# DDR3_LoongSon.net
KiCad netlist of a schematic drawn in Altium Designer
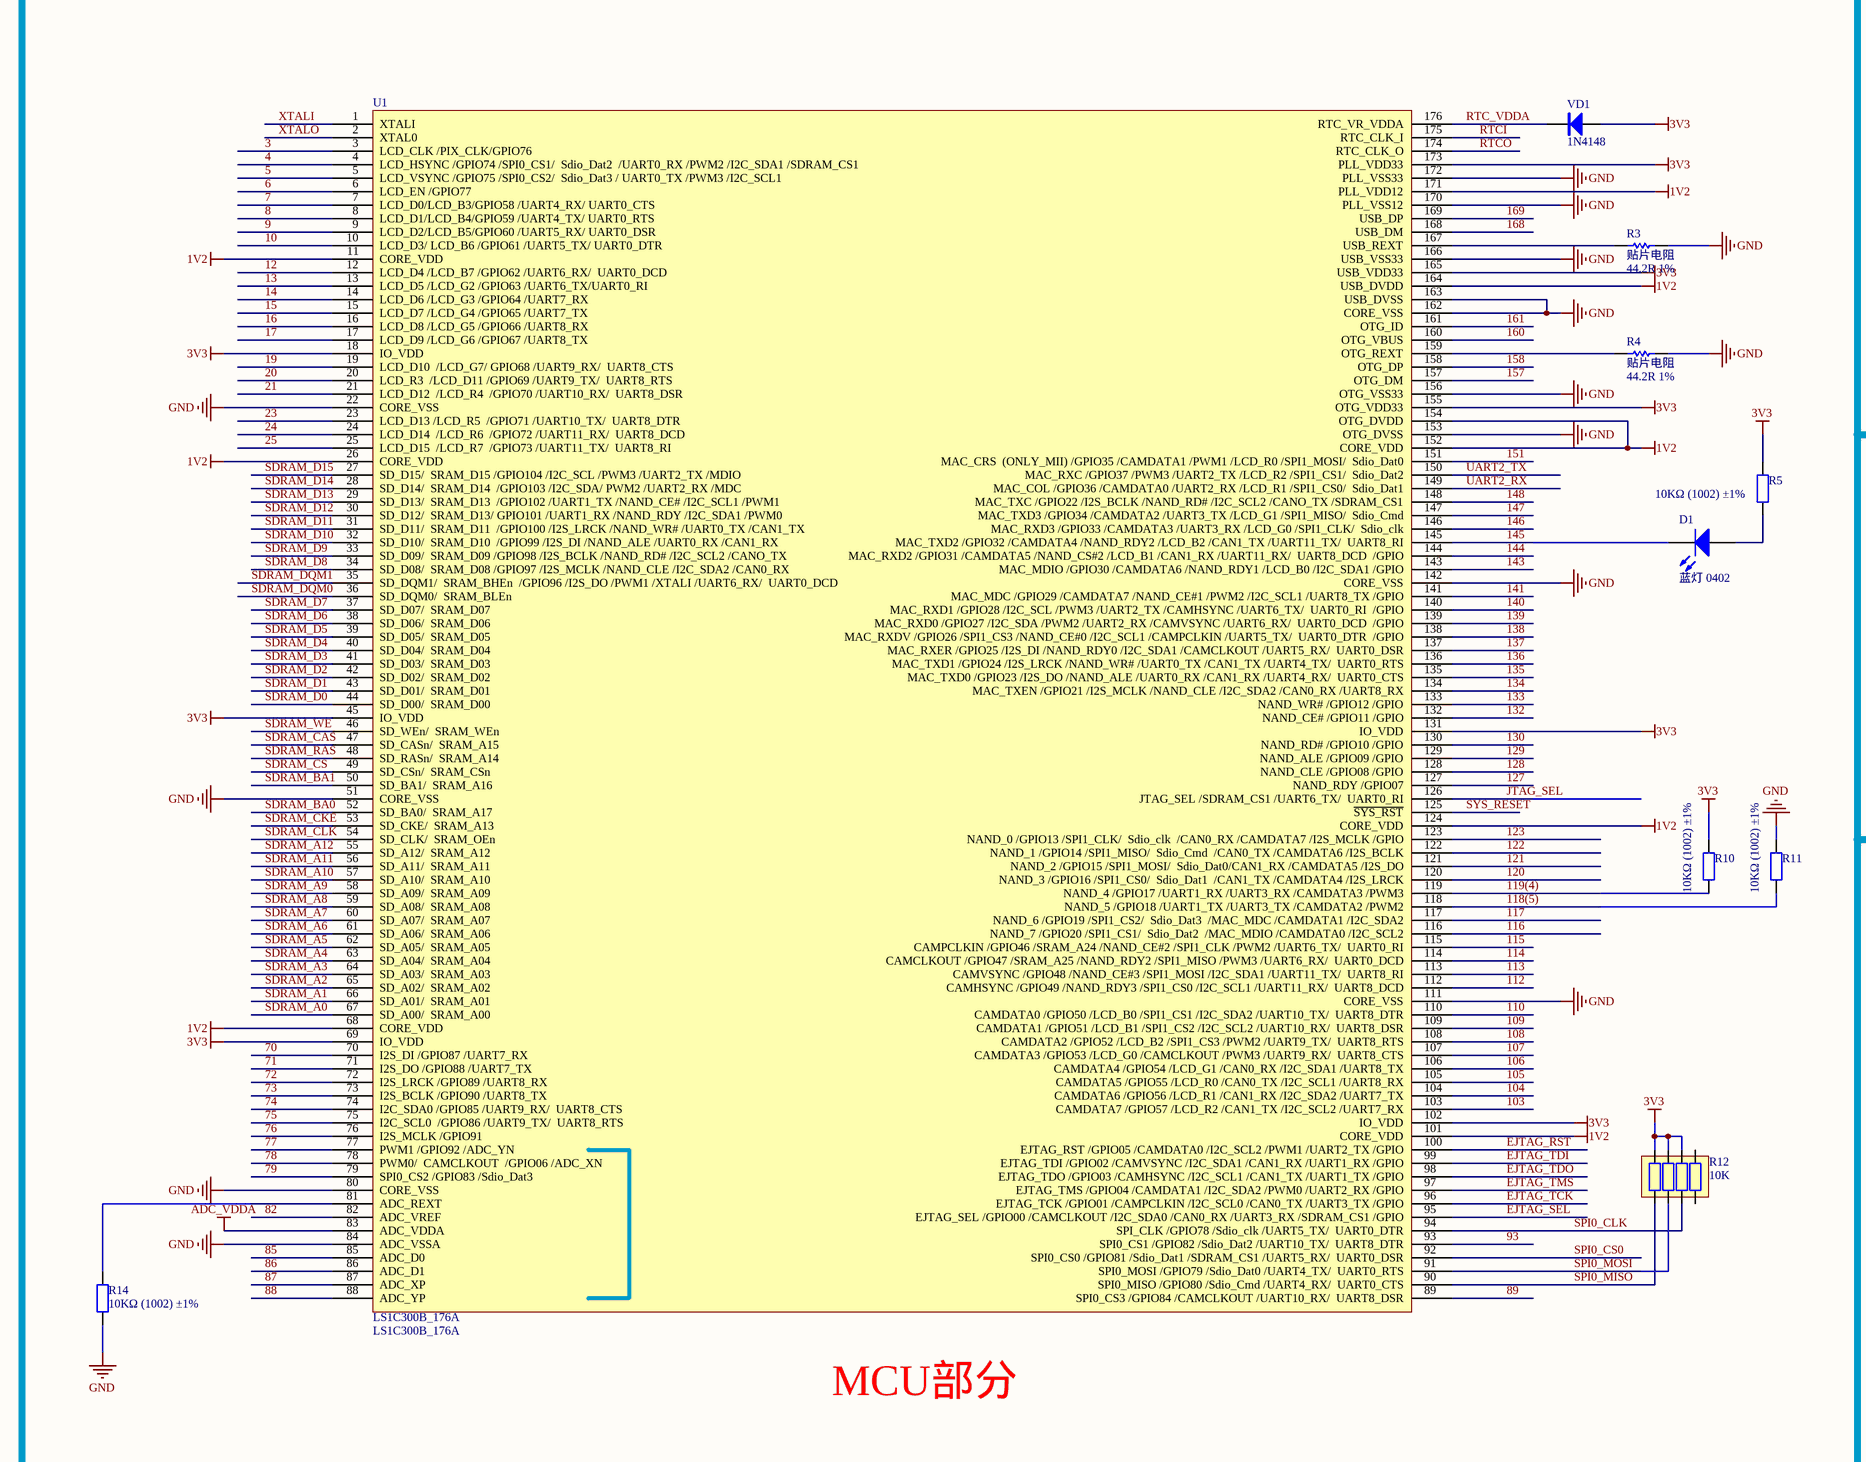
[diagram p0: DDR3_LoongSon.SchDoc, top left]
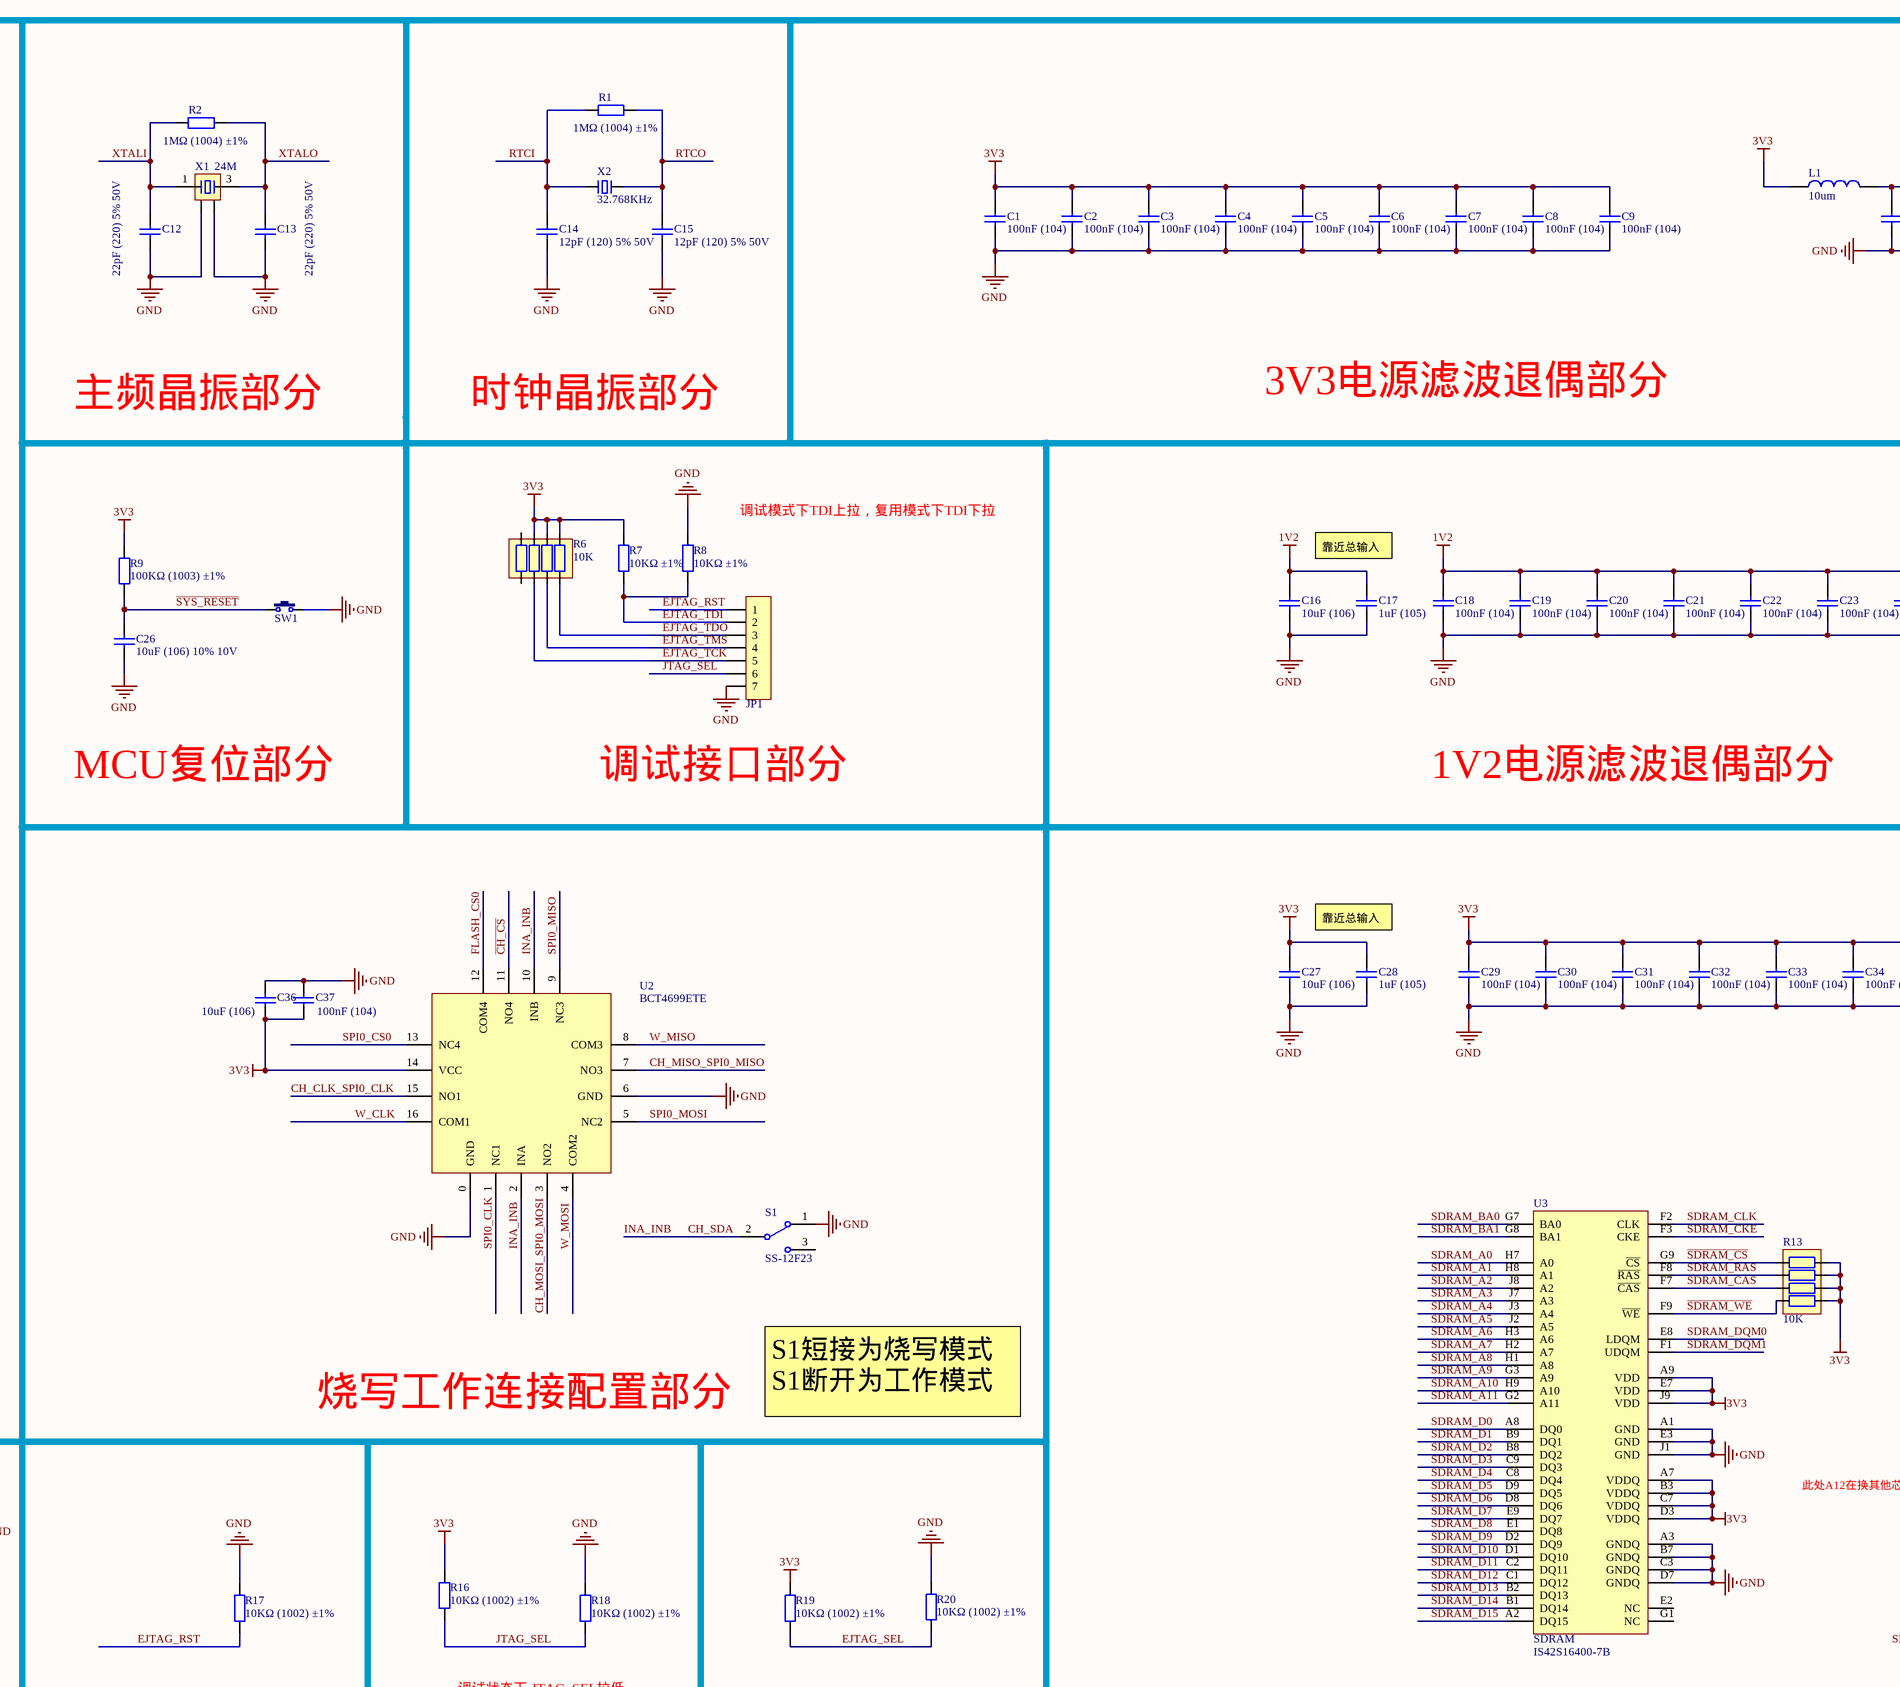
[diagram p1: DDR3_LoongSon.SchDoc, top middle]
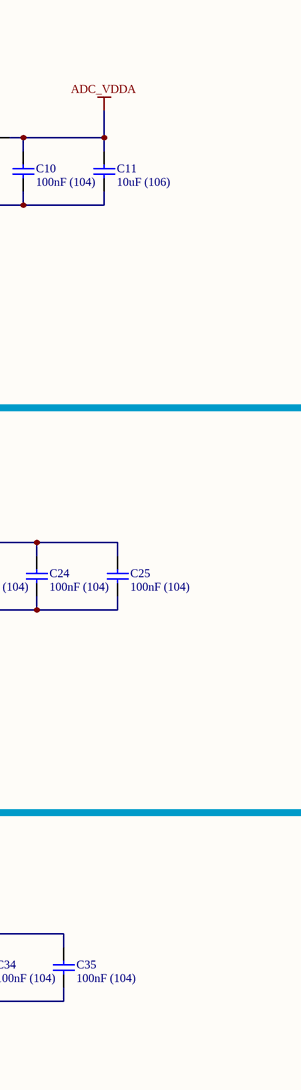
[diagram p2: DDR3_LoongSon.SchDoc, top right]
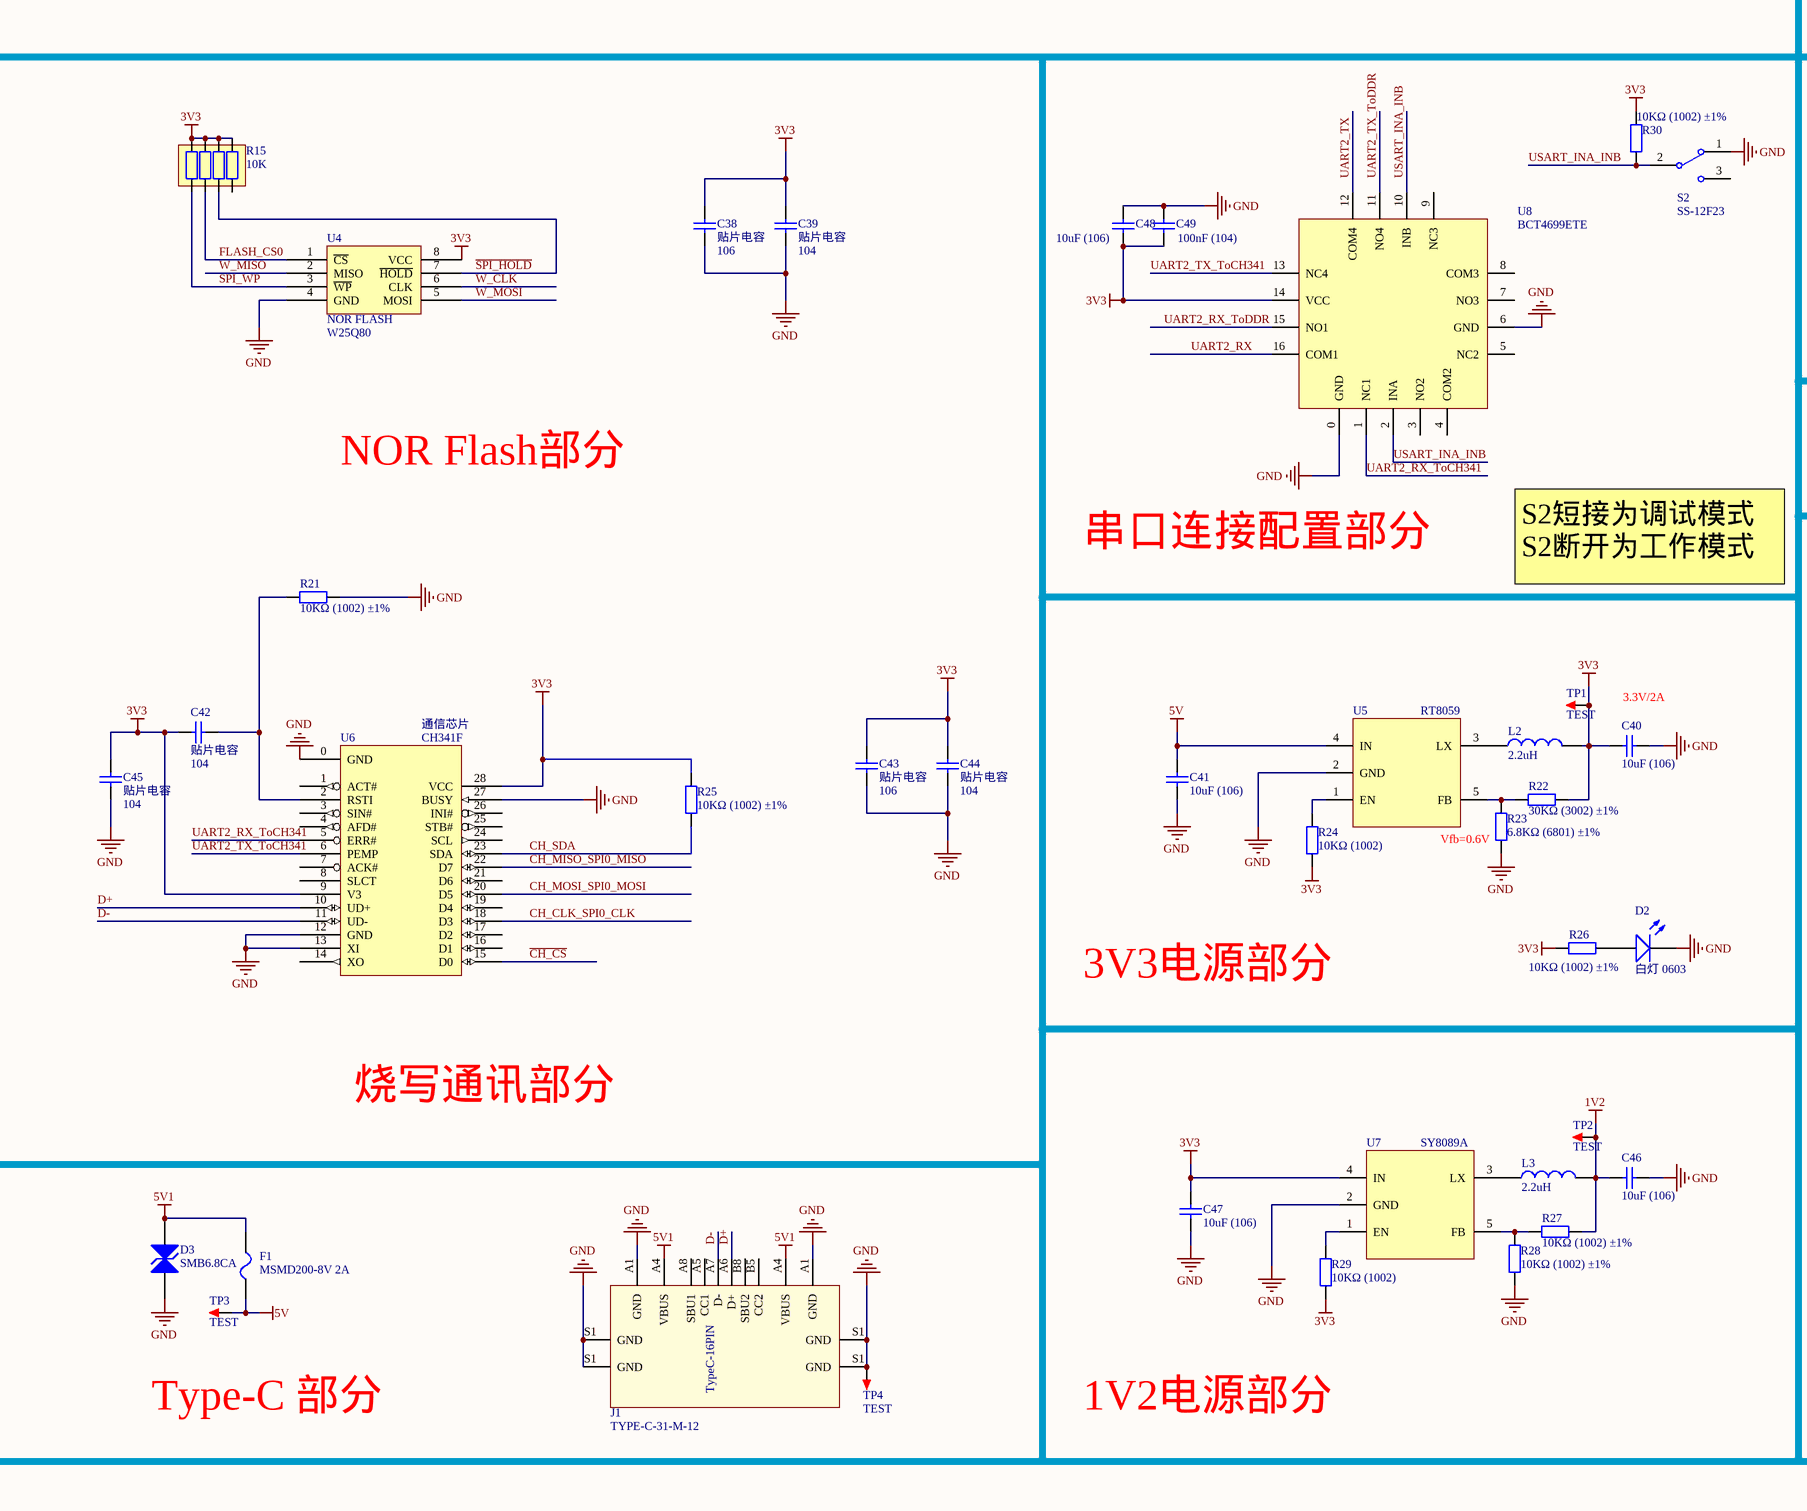
[diagram p3: DDR3_LoongSon.SchDoc, bottom left]
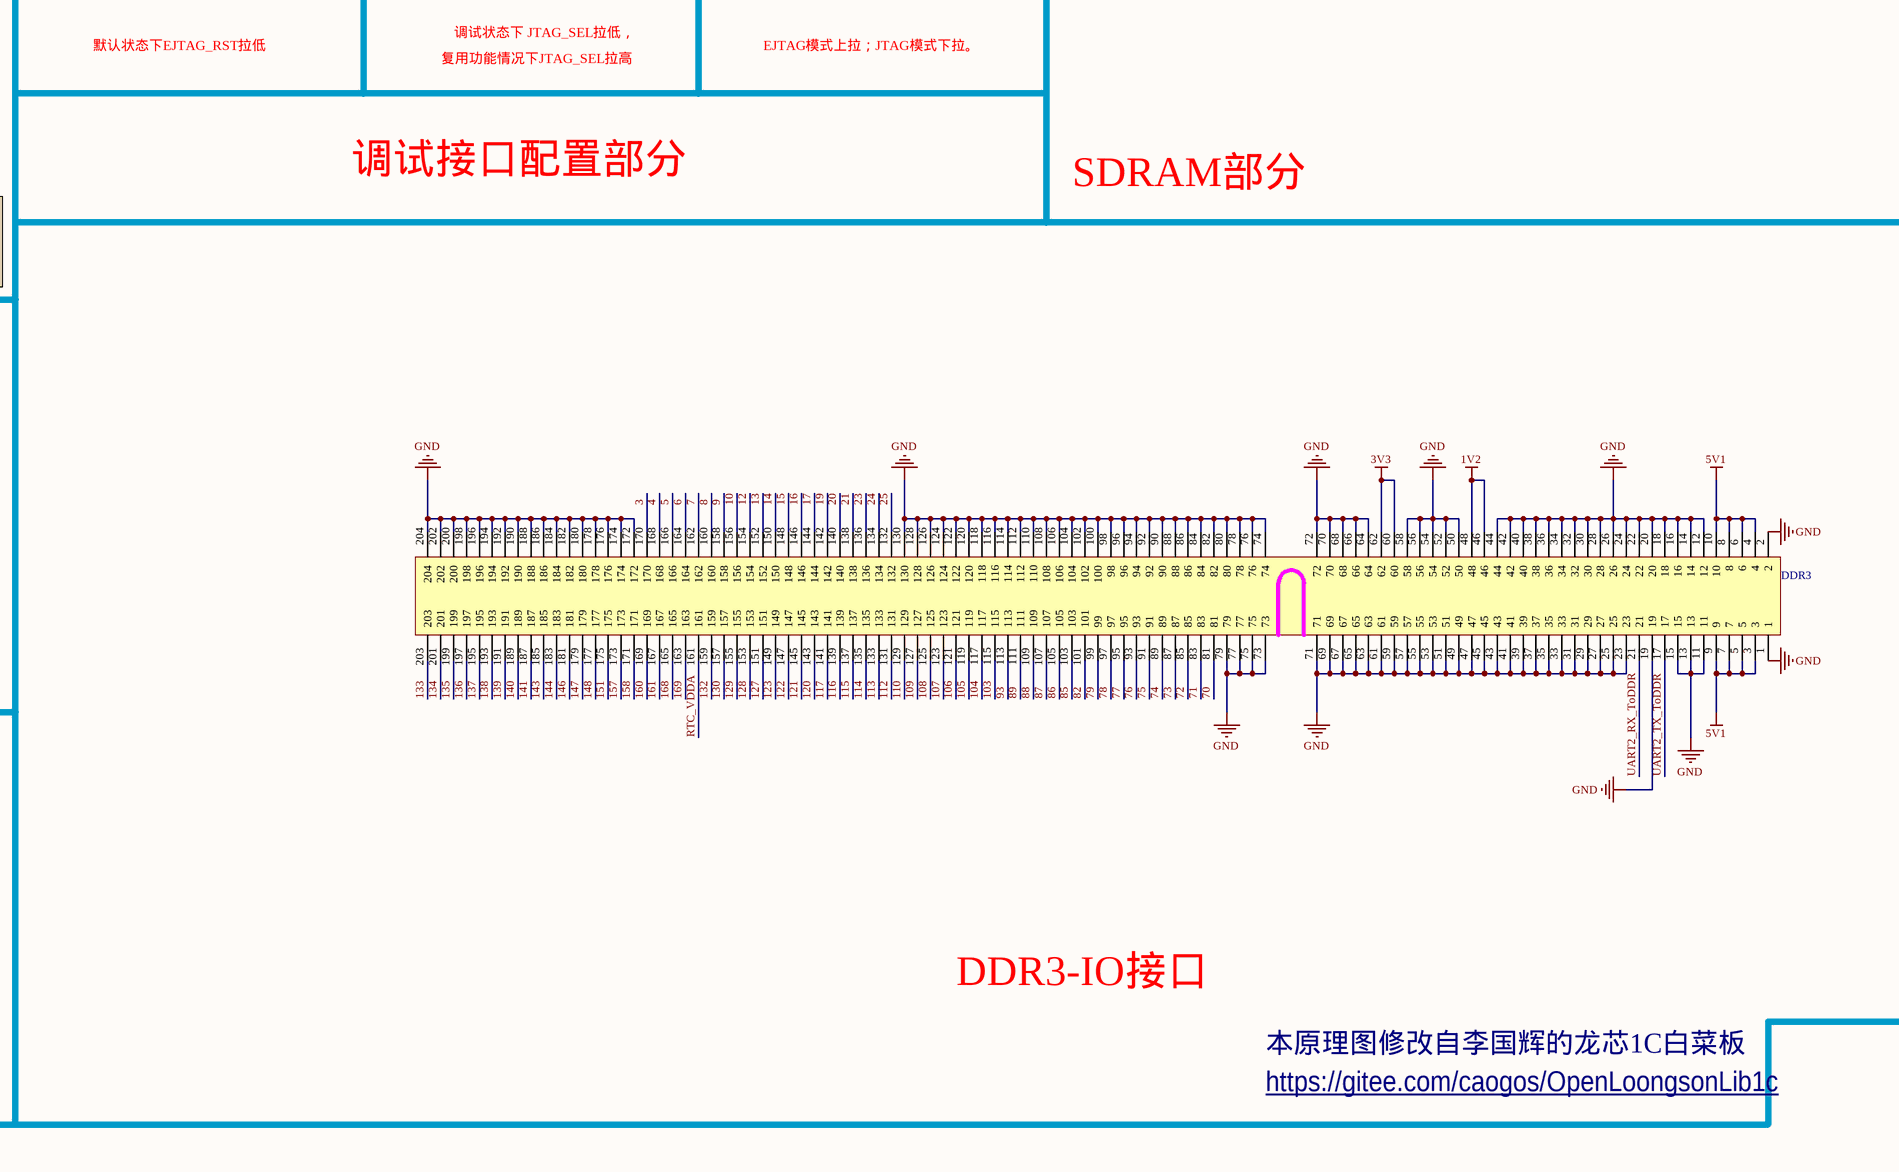
[diagram p4: DDR3_LoongSon.SchDoc, bottom middle]
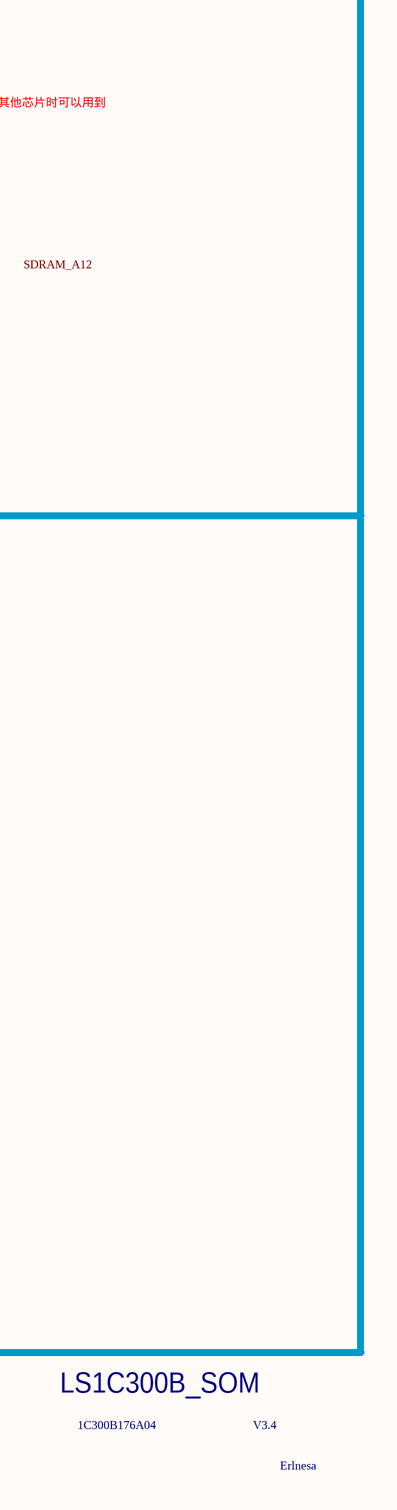
[diagram p5: DDR3_LoongSon.SchDoc, bottom right]

(export (version "E")
  (design (tool "Eeschema 10.0.6"))
  (components
    (comp (ref "C1")
      (value "100nF (104)")
      (footprint "LC-0402_C")
      (description "贴片电容")
      (libsource (lib "Miscellaneous Devices LC") (part "0603 100nF (104) 10% 50V"))
    )
    (comp (ref "C2")
      (value "100nF (104)")
      (footprint "LC-0402_C")
      (description "贴片电容")
      (libsource (lib "Miscellaneous Devices LC") (part "0603 100nF (104) 10% 50V"))
    )
    (comp (ref "C3")
      (value "100nF (104)")
      (footprint "LC-0402_C")
      (description "贴片电容")
      (libsource (lib "Miscellaneous Devices LC") (part "0603 100nF (104) 10% 50V"))
    )
    (comp (ref "C4")
      (value "100nF (104)")
      (footprint "LC-0402_C")
      (description "贴片电容")
      (libsource (lib "Miscellaneous Devices LC") (part "0603 100nF (104) 10% 50V"))
    )
    (comp (ref "C5")
      (value "100nF (104)")
      (footprint "LC-0402_C")
      (description "贴片电容")
      (libsource (lib "Miscellaneous Devices LC") (part "0603 100nF (104) 10% 50V"))
    )
    (comp (ref "C6")
      (value "100nF (104)")
      (footprint "LC-0402_C")
      (description "贴片电容")
      (libsource (lib "Miscellaneous Devices LC") (part "0603 100nF (104) 10% 50V"))
    )
    (comp (ref "C7")
      (value "100nF (104)")
      (footprint "LC-0402_C")
      (description "贴片电容")
      (libsource (lib "Miscellaneous Devices LC") (part "0603 100nF (104) 10% 50V"))
    )
    (comp (ref "C8")
      (value "100nF (104)")
      (footprint "LC-0402_C")
      (description "贴片电容")
      (libsource (lib "Miscellaneous Devices LC") (part "0603 100nF (104) 10% 50V"))
    )
    (comp (ref "C9")
      (value "100nF (104)")
      (footprint "LC-0402_C")
      (description "贴片电容")
      (libsource (lib "Miscellaneous Devices LC") (part "0603 100nF (104) 10% 50V"))
    )
    (comp (ref "C10")
      (value "100nF (104)")
      (footprint "LC-0402_C")
      (description "贴片电容")
      (libsource (lib "Miscellaneous Devices LC") (part "0603 100nF (104) 10% 50V"))
    )
    (comp (ref "C11")
      (value "10uF (106)")
      (footprint "LC-0402_C")
      (description "贴片电容")
      (libsource (lib "Miscellaneous Devices LC") (part "0603 10uF (106) 10% 10V"))
    )
    (comp (ref "C12")
      (value "22pF (220) 5% 50V")
      (footprint "LC-0402_C")
      (description "贴片电容")
      (libsource (lib "Miscellaneous Devices LC") (part "0603 22pF (220) 5% 50V"))
    )
    (comp (ref "C13")
      (value "22pF (220) 5% 50V")
      (footprint "LC-0402_C")
      (description "贴片电容")
      (libsource (lib "Miscellaneous Devices LC") (part "0603 22pF (220) 5% 50V"))
    )
    (comp (ref "C14")
      (value "12pF (120) 5% 50V")
      (footprint "LC-0402_C")
      (description "贴片电容")
      (libsource (lib "Miscellaneous Devices LC") (part "0603 12pF (120) 5% 50V"))
    )
    (comp (ref "C15")
      (value "12pF (120) 5% 50V")
      (footprint "LC-0402_C")
      (description "贴片电容")
      (libsource (lib "Miscellaneous Devices LC") (part "0603 12pF (120) 5% 50V"))
    )
    (comp (ref "C16")
      (value "10uF (106)")
      (footprint "LC-0402_C")
      (description "贴片电容")
      (libsource (lib "Miscellaneous Devices LC") (part "0603 10uF (106) 10% 10V"))
    )
    (comp (ref "C17")
      (value "1uF (105)")
      (footprint "LC-0402_C")
      (description "贴片电容")
      (libsource (lib "Miscellaneous Devices LC") (part "0603 1uF (105) 10% 50V"))
    )
    (comp (ref "C18")
      (value "100nF (104)")
      (footprint "LC-0402_C")
      (description "贴片电容")
      (libsource (lib "Miscellaneous Devices LC") (part "0603 100nF (104) 10% 50V"))
    )
    (comp (ref "C19")
      (value "100nF (104)")
      (footprint "LC-0402_C")
      (description "贴片电容")
      (libsource (lib "Miscellaneous Devices LC") (part "0603 100nF (104) 10% 50V"))
    )
    (comp (ref "C20")
      (value "100nF (104)")
      (footprint "LC-0402_C")
      (description "贴片电容")
      (libsource (lib "Miscellaneous Devices LC") (part "0603 100nF (104) 10% 50V"))
    )
    (comp (ref "C21")
      (value "100nF (104)")
      (footprint "LC-0402_C")
      (description "贴片电容")
      (libsource (lib "Miscellaneous Devices LC") (part "0603 100nF (104) 10% 50V"))
    )
    (comp (ref "C22")
      (value "100nF (104)")
      (footprint "LC-0402_C")
      (description "贴片电容")
      (libsource (lib "Miscellaneous Devices LC") (part "0603 100nF (104) 10% 50V"))
    )
    (comp (ref "C23")
      (value "100nF (104)")
      (footprint "LC-0402_C")
      (description "贴片电容")
      (libsource (lib "Miscellaneous Devices LC") (part "0603 100nF (104) 10% 50V"))
    )
    (comp (ref "C24")
      (value "100nF (104)")
      (footprint "LC-0402_C")
      (description "贴片电容")
      (libsource (lib "Miscellaneous Devices LC") (part "0603 100nF (104) 10% 50V"))
    )
    (comp (ref "C25")
      (value "100nF (104)")
      (footprint "LC-0402_C")
      (description "贴片电容")
      (libsource (lib "Miscellaneous Devices LC") (part "0603 100nF (104) 10% 50V"))
    )
    (comp (ref "C26")
      (value "10uF (106) 10% 10V")
      (footprint "LC-0402_C")
      (description "贴片电容")
      (libsource (lib "Miscellaneous Devices LC") (part "0603 10uF (106) 10% 10V"))
    )
    (comp (ref "C27")
      (value "10uF (106)")
      (footprint "LC-0402_C")
      (description "贴片电容")
      (libsource (lib "Miscellaneous Devices LC") (part "0603 10uF (106) 10% 10V"))
    )
    (comp (ref "C28")
      (value "1uF (105)")
      (footprint "LC-0402_C")
      (description "贴片电容")
      (libsource (lib "Miscellaneous Devices LC") (part "0603 1uF (105) 10% 50V"))
    )
    (comp (ref "C29")
      (value "100nF (104)")
      (footprint "LC-0402_C")
      (description "贴片电容")
      (libsource (lib "Miscellaneous Devices LC") (part "0603 100nF (104) 10% 50V"))
    )
    (comp (ref "C30")
      (value "100nF (104)")
      (footprint "LC-0402_C")
      (description "贴片电容")
      (libsource (lib "Miscellaneous Devices LC") (part "0603 100nF (104) 10% 50V"))
    )
    (comp (ref "C31")
      (value "100nF (104)")
      (footprint "LC-0402_C")
      (description "贴片电容")
      (libsource (lib "Miscellaneous Devices LC") (part "0603 100nF (104) 10% 50V"))
    )
    (comp (ref "C32")
      (value "100nF (104)")
      (footprint "LC-0402_C")
      (description "贴片电容")
      (libsource (lib "Miscellaneous Devices LC") (part "0603 100nF (104) 10% 50V"))
    )
    (comp (ref "C33")
      (value "100nF (104)")
      (footprint "LC-0402_C")
      (description "贴片电容")
      (libsource (lib "Miscellaneous Devices LC") (part "0603 100nF (104) 10% 50V"))
    )
    (comp (ref "C34")
      (value "100nF (104)")
      (footprint "LC-0402_C")
      (description "贴片电容")
      (libsource (lib "Miscellaneous Devices LC") (part "0603 100nF (104) 10% 50V"))
    )
    (comp (ref "C35")
      (value "100nF (104)")
      (footprint "LC-0402_C")
      (description "贴片电容")
      (libsource (lib "Miscellaneous Devices LC") (part "0603 100nF (104) 10% 50V"))
    )
    (comp (ref "C36")
      (value "10uF (106)")
      (footprint "LC-0402_C")
      (description "贴片电容")
      (libsource (lib "Miscellaneous Devices LC") (part "0603 10uF (106) 10% 10V"))
    )
    (comp (ref "C37")
      (value "100nF (104)")
      (footprint "LC-0402_C")
      (description "贴片电容")
      (libsource (lib "Miscellaneous Devices LC") (part "0603 100nF (104) 10% 50V"))
    )
    (comp (ref "C38")
      (value "贴片电容")
      (footprint "LC-0402_C")
      (description "Capacitor")
      (fields (field (name "ALTIUM_VALUE") "106") (field (name "PUBLISHER") "Altium Limited"))
      (libsource (lib "Miscellaneous Devices") (part "Cap"))
    )
    (comp (ref "C39")
      (value "贴片电容")
      (footprint "LC-0402_C")
      (description "Capacitor")
      (fields (field (name "ALTIUM_VALUE") "104") (field (name "PUBLISHER") "Altium Limited"))
      (libsource (lib "Miscellaneous Devices") (part "Cap"))
    )
    (comp (ref "C40")
      (value "10uF (106)")
      (footprint "LC-0603_C")
      (description "贴片电容")
      (libsource (lib "Miscellaneous Devices LC") (part "0603 10uF (106) 10% 10V"))
    )
    (comp (ref "C41")
      (value "10uF (106)")
      (footprint "LC-0603_C")
      (description "贴片电容")
      (libsource (lib "Miscellaneous Devices LC") (part "0603 10uF (106) 10% 10V"))
    )
    (comp (ref "C42")
      (value "贴片电容")
      (footprint "LC-0402_C")
      (description "Capacitor")
      (fields (field (name "ALTIUM_VALUE") "104") (field (name "PUBLISHER") "Altium Limited"))
      (libsource (lib "Miscellaneous Devices") (part "Cap"))
    )
    (comp (ref "C43")
      (value "贴片电容")
      (footprint "LC-0402_C")
      (description "Capacitor")
      (fields (field (name "ALTIUM_VALUE") "106") (field (name "PUBLISHER") "Altium Limited"))
      (libsource (lib "Miscellaneous Devices") (part "Cap"))
    )
    (comp (ref "C44")
      (value "贴片电容")
      (footprint "LC-0402_C")
      (description "Capacitor")
      (fields (field (name "ALTIUM_VALUE") "104") (field (name "PUBLISHER") "Altium Limited"))
      (libsource (lib "Miscellaneous Devices") (part "Cap"))
    )
    (comp (ref "C45")
      (value "贴片电容")
      (footprint "LC-0402_C")
      (description "Capacitor")
      (fields (field (name "ALTIUM_VALUE") "104") (field (name "PUBLISHER") "Altium Limited"))
      (libsource (lib "Miscellaneous Devices") (part "Cap"))
    )
    (comp (ref "C46")
      (value "10uF (106)")
      (footprint "LC-0603_C")
      (description "贴片电容")
      (libsource (lib "Miscellaneous Devices LC") (part "0603 10uF (106) 10% 10V"))
    )
    (comp (ref "C47")
      (value "10uF (106)")
      (footprint "LC-0603_C")
      (description "贴片电容")
      (libsource (lib "Miscellaneous Devices LC") (part "0603 10uF (106) 10% 10V"))
    )
    (comp (ref "C48")
      (value "10uF (106)")
      (footprint "LC-0603_C")
      (description "贴片电容")
      (libsource (lib "Miscellaneous Devices LC") (part "0603 10uF (106) 10% 10V"))
    )
    (comp (ref "C49")
      (value "100nF (104)")
      (footprint "LC-0603_C")
      (description "贴片电容")
      (libsource (lib "Miscellaneous Devices LC") (part "0603 100nF (104) 10% 50V"))
    )
    (comp (ref "D1")
      (value "蓝灯 0402")
      (footprint "LC-0603_LED_S1")
      (description "发光二极管")
      (libsource (lib "Miscellaneous Devices LC") (part "0603 蓝灯"))
    )
    (comp (ref "D2")
      (value "白灯 0603")
      (footprint "LC-0603_LED_S1")
      (description "发光二极管")
      (libsource (lib "Miscellaneous Devices LC") (part "0603 白灯"))
    )
    (comp (ref "D3")
      (value "SMB6.8CA")
      (footprint "LC-SMB(DO-214AA)_S1")
      (description "TVS")
      (libsource (lib "Miscellaneous Devices LC") (part "SMB/DO-214AA P6SMB6.8CA"))
    )
    (comp (ref "DDR1") (value "DDR3") (footprint "DDR3_PLUG_R") (libsource (lib "Type-C") (part "DDR3")))
    (comp (ref "F1")
      (value "MSMD200-8V 2A")
      (footprint "FU 1206")
      (description "贴片保险丝")
      (fields (field (name "版权归属") "源创客"))
      (libsource (lib "保险丝-晶振") (part "FU"))
    )
    (comp (ref "J1")
      (value "TYPE-C-31-M-12")
      (footprint "TYPE-C-31-M-12")
      (libsource (lib "Type-C") (part "TYPE-C-31-M-12"))
    )
    (comp (ref "JP1")
      (value "HDR-1X7")
      (footprint "HDR-1X7")
      (description "7P接插件")
      (fields (field (name "版权归属") "源创客"))
      (libsource (lib "接插件") (part "Header 7"))
    )
    (comp (ref "L1")
      (value "10um")
      (footprint "LC-0402_L")
      (description "小功率贴片电感")
      (fields (field (name "版权归属") "源创客"))
      (libsource (lib "电阻-电容-电感") (part "L"))
    )
    (comp (ref "L2")
      (value "2.2uH")
      (footprint "2520-L")
      (description "小功率贴片电感")
      (fields (field (name "版权归属") "源创客"))
      (libsource (lib "电阻-电容-电感") (part "L"))
    )
    (comp (ref "L3")
      (value "2.2uH")
      (footprint "2520-L")
      (description "小功率贴片电感")
      (fields (field (name "版权归属") "源创客"))
      (libsource (lib "电阻-电容-电感") (part "L"))
    )
    (comp (ref "R1")
      (value "1MΩ (1004) ±1%")
      (footprint "LC-0402_R")
      (description "贴片电阻")
      (libsource (lib "Miscellaneous Devices LC") (part "0603 1MΩ (1004) 1%"))
    )
    (comp (ref "R2")
      (value "1MΩ (1004) ±1%")
      (footprint "LC-0402_R")
      (description "贴片电阻")
      (libsource (lib "Miscellaneous Devices LC") (part "0603 1MΩ (1004) 1%"))
    )
    (comp (ref "R3")
      (value "贴片电阻")
      (footprint "LC-0402_R")
      (description "Resistor")
      (fields (field (name "ALTIUM_VALUE") "44.2R 1%") (field (name "PUBLISHER") "Altium Limited"))
      (libsource (lib "Miscellaneous Devices") (part "Res1"))
    )
    (comp (ref "R4")
      (value "贴片电阻")
      (footprint "LC-0402_R")
      (description "Resistor")
      (fields (field (name "ALTIUM_VALUE") "44.2R 1%") (field (name "PUBLISHER") "Altium Limited"))
      (libsource (lib "Miscellaneous Devices") (part "Res1"))
    )
    (comp (ref "R5")
      (value "10KΩ (1002) ±1%")
      (footprint "LC-0402_R")
      (description "贴片电阻")
      (libsource (lib "Miscellaneous Devices LC") (part "0603 10KΩ (1002) 1%"))
    )
    (comp (ref "R6")
      (value "10K")
      (footprint "LC-0402_Rx4")
      (description "贴片网络排阻")
      (fields (field (name "版权归属") "源创客"))
      (libsource (lib "电阻-电容-电感") (part "R-8P4R"))
    )
    (comp (ref "R7")
      (value "10KΩ ±1%")
      (footprint "LC-0402_R")
      (description "贴片电阻")
      (libsource (lib "Miscellaneous Devices LC") (part "0402 10KΩ (1002) 1%"))
    )
    (comp (ref "R8")
      (value "10KΩ ±1%")
      (footprint "LC-0402_R")
      (description "贴片电阻")
      (libsource (lib "Miscellaneous Devices LC") (part "0402 10KΩ (1002) 1%"))
    )
    (comp (ref "R9")
      (value "100KΩ (1003) ±1%")
      (footprint "LC-0402_R")
      (description "贴片电阻")
      (libsource (lib "Miscellaneous Devices LC") (part "0603 100KΩ (1003) 1%"))
    )
    (comp (ref "R10")
      (value "10KΩ (1002) ±1%")
      (footprint "LC-0402_R")
      (description "贴片电阻")
      (libsource (lib "Miscellaneous Devices LC") (part "0603 10KΩ (1002) 1%"))
    )
    (comp (ref "R11")
      (value "10KΩ (1002) ±1%")
      (footprint "LC-0402_R")
      (description "贴片电阻")
      (libsource (lib "Miscellaneous Devices LC") (part "0603 10KΩ (1002) 1%"))
    )
    (comp (ref "R12")
      (value "10K")
      (footprint "LC-0402_Rx4")
      (description "贴片网络排阻")
      (fields (field (name "版权归属") "源创客"))
      (libsource (lib "电阻-电容-电感") (part "R-8P4R"))
    )
    (comp (ref "R13")
      (value "10K")
      (footprint "LC-0402_Rx4")
      (description "贴片网络排阻")
      (fields (field (name "版权归属") "源创客"))
      (libsource (lib "") (part "R-8P4R_1"))
    )
    (comp (ref "R14")
      (value "10KΩ (1002) ±1%")
      (footprint "LC-0402_R")
      (description "贴片电阻")
      (libsource (lib "Miscellaneous Devices LC") (part "0603 10KΩ (1002) 1%"))
    )
    (comp (ref "R15")
      (value "10K")
      (footprint "LC-0402_Rx4")
      (description "贴片网络排阻")
      (fields (field (name "版权归属") "源创客"))
      (libsource (lib "电阻-电容-电感") (part "R-8P4R"))
    )
    (comp (ref "R16")
      (value "10KΩ (1002) ±1%")
      (footprint "LC-0402_R")
      (description "贴片电阻")
      (libsource (lib "Miscellaneous Devices LC") (part "0603 10KΩ (1002) 1%"))
    )
    (comp (ref "R17")
      (value "10KΩ (1002) ±1%")
      (footprint "LC-0402_R")
      (description "贴片电阻")
      (libsource (lib "Miscellaneous Devices LC") (part "0603 10KΩ (1002) 1%"))
    )
    (comp (ref "R18")
      (value "10KΩ (1002) ±1%")
      (footprint "LC-0402_R")
      (description "贴片电阻")
      (libsource (lib "Miscellaneous Devices LC") (part "0603 10KΩ (1002) 1%"))
    )
    (comp (ref "R19")
      (value "10KΩ (1002) ±1%")
      (footprint "LC-0402_R")
      (description "贴片电阻")
      (libsource (lib "Miscellaneous Devices LC") (part "0603 10KΩ (1002) 1%"))
    )
    (comp (ref "R20")
      (value "10KΩ (1002) ±1%")
      (footprint "LC-0402_R")
      (description "贴片电阻")
      (libsource (lib "Miscellaneous Devices LC") (part "0603 10KΩ (1002) 1%"))
    )
    (comp (ref "R21")
      (value "10KΩ (1002) ±1%")
      (footprint "LC-0402_R")
      (description "贴片电阻")
      (libsource (lib "") (part "0603 10KΩ (1002) 1%_1"))
    )
    (comp (ref "R22")
      (value "30KΩ (3002) ±1%")
      (footprint "LC-0603_R")
      (description "贴片电阻")
      (libsource (lib "Miscellaneous Devices LC") (part "0603 30KΩ (3002) 1%"))
    )
    (comp (ref "R23")
      (value "6.8KΩ (6801) ±1%")
      (footprint "LC-0603_R")
      (description "贴片电阻")
      (libsource (lib "Miscellaneous Devices LC") (part "0603 6.8KΩ (6801) 1%"))
    )
    (comp (ref "R24")
      (value "10KΩ (1002)")
      (footprint "LC-0603_R")
      (description "贴片电阻")
      (libsource (lib "Miscellaneous Devices LC") (part "0603 10KΩ (1002) 1%"))
    )
    (comp (ref "R25")
      (value "10KΩ (1002) ±1%")
      (footprint "LC-0402_R")
      (description "贴片电阻")
      (libsource (lib "Miscellaneous Devices LC") (part "0603 10KΩ (1002) 1%"))
    )
    (comp (ref "R26")
      (value "10KΩ (1002) ±1%")
      (footprint "LC-0603_R")
      (description "贴片电阻")
      (libsource (lib "") (part "0603 10KΩ (1002) 1%_1"))
    )
    (comp (ref "R27")
      (value "10KΩ (1002) ±1%")
      (footprint "LC-0603_R")
      (description "贴片电阻")
      (libsource (lib "") (part "0603 10KΩ (1002) 1%_1"))
    )
    (comp (ref "R28")
      (value "10KΩ (1002) ±1%")
      (footprint "LC-0603_R")
      (description "贴片电阻")
      (libsource (lib "Miscellaneous Devices LC") (part "0603 10KΩ (1002) 1%"))
    )
    (comp (ref "R29")
      (value "10KΩ (1002)")
      (footprint "LC-0603_R")
      (description "贴片电阻")
      (libsource (lib "Miscellaneous Devices LC") (part "0603 10KΩ (1002) 1%"))
    )
    (comp (ref "R30")
      (value "10KΩ (1002) ±1%")
      (footprint "LC-0603_R")
      (description "贴片电阻")
      (libsource (lib "Miscellaneous Devices LC") (part "0603 10KΩ (1002) 1%"))
    )
    (comp (ref "S1")
      (value "SS-12F23")
      (footprint "MSK-12C01-07")
      (description "1路波动开关")
      (fields (field (name "版权归属") "源创客"))
      (libsource (lib "按键-开关") (part "SSW-1P"))
    )
    (comp (ref "S2")
      (value "SS-12F23")
      (footprint "MSK-12C01-07")
      (description "1路波动开关")
      (fields (field (name "版权归属") "源创客"))
      (libsource (lib "按键-开关") (part "SSW-1P"))
    )
    (comp (ref "SW1")
      (value "3x6x5")
      (footprint "TSW SMD-3*6*2.5")
      (description "3x6轻触开关")
      (fields (field (name "版权归属") "源创客"))
      (libsource (lib "按键-开关") (part "TSW 3x6"))
    )
    (comp (ref "TP1")
      (value "TEST")
      (footprint "TEST 1")
      (description "测试点")
      (fields (field (name "版权归属") "源创客"))
      (libsource (lib "未分类器件") (part "TEST"))
    )
    (comp (ref "TP2")
      (value "TEST")
      (footprint "TEST 1")
      (description "测试点")
      (fields (field (name "版权归属") "源创客"))
      (libsource (lib "未分类器件") (part "TEST"))
    )
    (comp (ref "TP3")
      (value "TEST")
      (footprint "TEST 1")
      (description "测试点")
      (fields (field (name "版权归属") "源创客"))
      (libsource (lib "未分类器件") (part "TEST"))
    )
    (comp (ref "TP4")
      (value "TEST")
      (footprint "TEST 1")
      (description "测试点")
      (fields (field (name "版权归属") "源创客"))
      (libsource (lib "未分类器件") (part "TEST"))
    )
    (comp (ref "U1")
      (value "LS1C300B_176A")
      (footprint "QFP176")
      (description "龙芯1C300B QFP176A")
      (fields (field (name "ALTIUM_VALUE") "LS1C300B_176A"))
      (libsource (lib "Type-C") (part "LS1C300B_176A"))
    )
    (comp (ref "U2")
      (value "BCT4699ETE")
      (footprint "TQFN16-3X3")
      (description "四通单刀双掷道模拟开关")
      (libsource (lib "Type-C") (part "BCT4699ETE"))
    )
    (comp (ref "U3")
      (value "SDRAM")
      (footprint "BGA-54_L8.0-W8.0-R9-C6-P0.80-TL")
      (description "ISSI 公司SDRAM ， 166, 133, 100 MHz")
      (fields (field (name "ALTIUM_VALUE") "IS42S16400-7B"))
      (libsource (lib "Type-C") (part "IS42S16400_7B"))
    )
    (comp (ref "U4")
      (value "NOR FLASH")
      (footprint "WSON-8_L5.0-W6.0-P1.27-BL-EP")
      (description "nor flash W25Q64....华邦")
      (fields (field (name "ALTIUM_VALUE") "W25Q80"))
      (libsource (lib "Type-C") (part "W25Q80BV"))
    )
    (comp (ref "U5")
      (value "RT8059")
      (footprint "SOT23-5N")
      (description "LDO")
      (libsource (lib "Type-C") (part "RT8059"))
    )
    (comp (ref "U6")
      (value "通信芯片")
      (footprint "QFN28-4X4")
      (description "USB to Print Port / Parallel")
      (fields (field (name "ALTIUM_VALUE") "CH341F"))
      (libsource (lib "Type-C") (part "CH341F"))
    )
    (comp (ref "U7")
      (value "SY8089A")
      (footprint "SOT23-5N")
      (description "LDO")
      (libsource (lib "Type-C") (part "SY8089A"))
    )
    (comp (ref "U8")
      (value "BCT4699ETE")
      (footprint "TQFN16-3X3")
      (description "四通单刀双掷道模拟开关")
      (libsource (lib "Type-C") (part "BCT4699ETE"))
    )
    (comp (ref "VD1")
      (value "1N4148")
      (footprint "MINI_MELF (LL34)")
      (description "高速开关二极管")
      (fields (field (name "版权归属") "源创客"))
      (libsource (lib "二极管-整流桥") (part "1N4148"))
    )
    (comp (ref "X1")
      (value "24M")
      (footprint "XTAL-3225")
      (description "4脚晶振")
      (fields (field (name "版权归属") "源创客"))
      (libsource (lib "保险丝-晶振") (part "XTAL-4"))
    )
    (comp (ref "X2")
      (value "32.768KHz")
      (footprint "XTAL-3215")
      (description "2脚晶振")
      (fields (field (name "版权归属") "源创客"))
      (libsource (lib "保险丝-晶振") (part "XTAL-2"))
    )
  )
  (nets
    (net (code "1") (name "/3") (class "Default")
      (node (ref "DDR1") (pin "170") (pinfunction "170_170") (pintype "passive"))
      (node (ref "U1") (pin "3") (pinfunction "LCD_CLK_/PIX_CLK/GPIO76_3") (pintype "passive"))
    )
    (net (code "2") (name "/4") (class "Default")
      (node (ref "DDR1") (pin "168") (pinfunction "168_168") (pintype "passive"))
      (node (ref "U1") (pin "4") (pinfunction "LCD_HSYNC_/GPIO74_/SPI0_CS1/__Sdio_Dat2__/UART0_RX_/PWM2_/I2C_SDA1_/SDRAM_CS1_4") (pintype "passive"))
    )
    (net (code "3") (name "/5") (class "Default")
      (node (ref "DDR1") (pin "166") (pinfunction "166_166") (pintype "passive"))
      (node (ref "U1") (pin "5") (pinfunction "LCD_VSYNC_/GPIO75_/SPI0_CS2/__Sdio_Dat3_/_UART0_TX_/PWM3_/I2C_SCL1_5") (pintype "passive"))
    )
    (net (code "4") (name "/6") (class "Default")
      (node (ref "DDR1") (pin "164") (pinfunction "164_164") (pintype "passive"))
      (node (ref "U1") (pin "6") (pinfunction "LCD_EN_/GPIO77_6") (pintype "passive"))
    )
    (net (code "5") (name "/7") (class "Default")
      (node (ref "DDR1") (pin "162") (pinfunction "162_162") (pintype "passive"))
      (node (ref "U1") (pin "7") (pinfunction "LCD_D0/LCD_B3/GPIO58_/UART4_RX/_UART0_CTS_7") (pintype "passive"))
    )
    (net (code "6") (name "/8") (class "Default")
      (node (ref "DDR1") (pin "160") (pinfunction "160_160") (pintype "passive"))
      (node (ref "U1") (pin "8") (pinfunction "LCD_D1/LCD_B4/GPIO59_/UART4_TX/_UART0_RTS_8") (pintype "passive"))
    )
    (net (code "7") (name "/9") (class "Default")
      (node (ref "DDR1") (pin "158") (pinfunction "158_158") (pintype "passive"))
      (node (ref "U1") (pin "9") (pinfunction "LCD_D2/LCD_B5/GPIO60_/UART5_RX/_UART0_DSR_9") (pintype "passive"))
    )
    (net (code "8") (name "/10") (class "Default")
      (node (ref "DDR1") (pin "156") (pinfunction "156_156") (pintype "passive"))
      (node (ref "U1") (pin "10") (pinfunction "LCD_D3/_LCD_B6_/GPIO61_/UART5_TX/_UART0_DTR_10") (pintype "passive"))
    )
    (net (code "9") (name "/12") (class "Default")
      (node (ref "DDR1") (pin "154") (pinfunction "154_154") (pintype "passive"))
      (node (ref "U1") (pin "12") (pinfunction "LCD_D4_/LCD_B7_/GPIO62_/UART6_RX/__UART0_DCD_12") (pintype "passive"))
    )
    (net (code "10") (name "/13") (class "Default")
      (node (ref "DDR1") (pin "152") (pinfunction "152_152") (pintype "passive"))
      (node (ref "U1") (pin "13") (pinfunction "LCD_D5_/LCD_G2_/GPIO63_/UART6_TX/UART0_RI_13") (pintype "passive"))
    )
    (net (code "11") (name "/14") (class "Default")
      (node (ref "DDR1") (pin "150") (pinfunction "150_150") (pintype "passive"))
      (node (ref "U1") (pin "14") (pinfunction "LCD_D6_/LCD_G3_/GPIO64_/UART7_RX_14") (pintype "passive"))
    )
    (net (code "12") (name "/15") (class "Default")
      (node (ref "DDR1") (pin "148") (pinfunction "148_148") (pintype "passive"))
      (node (ref "U1") (pin "15") (pinfunction "LCD_D7_/LCD_G4_/GPIO65_/UART7_TX_15") (pintype "passive"))
    )
    (net (code "13") (name "/16") (class "Default")
      (node (ref "DDR1") (pin "146") (pinfunction "146_146") (pintype "passive"))
      (node (ref "U1") (pin "16") (pinfunction "LCD_D8_/LCD_G5_/GPIO66_/UART8_RX_16") (pintype "passive"))
    )
    (net (code "14") (name "/17") (class "Default")
      (node (ref "DDR1") (pin "144") (pinfunction "144_144") (pintype "passive"))
      (node (ref "U1") (pin "17") (pinfunction "LCD_D9_/LCD_G6_/GPIO67_/UART8_TX_17") (pintype "passive"))
    )
    (net (code "15") (name "/19") (class "Default")
      (node (ref "DDR1") (pin "142") (pinfunction "142_142") (pintype "passive"))
      (node (ref "U1") (pin "19") (pinfunction "LCD_D10__/LCD_G7/_GPIO68_/UART9_RX/__UART8_CTS_19") (pintype "passive"))
    )
    (net (code "16") (name "/20") (class "Default")
      (node (ref "DDR1") (pin "140") (pinfunction "140_140") (pintype "passive"))
      (node (ref "U1") (pin "20") (pinfunction "LCD_R3__/LCD_D11_/GPIO69_/UART9_TX/__UART8_RTS_20") (pintype "passive"))
    )
    (net (code "17") (name "/21") (class "Default")
      (node (ref "DDR1") (pin "138") (pinfunction "138_138") (pintype "passive"))
      (node (ref "U1") (pin "21") (pinfunction "LCD_D12__/LCD_R4__/GPIO70_/UART10_RX/__UART8_DSR_21") (pintype "passive"))
    )
    (net (code "18") (name "/23") (class "Default")
      (node (ref "DDR1") (pin "136") (pinfunction "136_136") (pintype "passive"))
      (node (ref "U1") (pin "23") (pinfunction "LCD_D13_/LCD_R5__/GPIO71_/UART10_TX/__UART8_DTR_23") (pintype "passive"))
    )
    (net (code "19") (name "/24") (class "Default")
      (node (ref "DDR1") (pin "134") (pinfunction "134_134") (pintype "passive"))
      (node (ref "U1") (pin "24") (pinfunction "LCD_D14__/LCD_R6__/GPIO72_/UART11_RX/__UART8_DCD_24") (pintype "passive"))
    )
    (net (code "20") (name "/25") (class "Default")
      (node (ref "DDR1") (pin "132") (pinfunction "132_132") (pintype "passive"))
      (node (ref "U1") (pin "25") (pinfunction "LCD_D15__/LCD_R7__/GPIO73_/UART11_TX/__UART8_RI_25") (pintype "passive"))
    )
    (net (code "21") (name "/70") (class "Default")
      (node (ref "DDR1") (pin "81") (pinfunction "81_81") (pintype "passive"))
      (node (ref "U1") (pin "70") (pinfunction "I2S_DI_/GPIO87_/UART7_RX_70") (pintype "passive"))
    )
    (net (code "22") (name "/71") (class "Default")
      (node (ref "DDR1") (pin "83") (pinfunction "83_83") (pintype "passive"))
      (node (ref "U1") (pin "71") (pinfunction "I2S_DO_/GPIO88_/UART7_TX_71") (pintype "passive"))
    )
    (net (code "23") (name "/72") (class "Default")
      (node (ref "DDR1") (pin "85") (pinfunction "85_85") (pintype "passive"))
      (node (ref "U1") (pin "72") (pinfunction "I2S_LRCK_/GPIO89_/UART8_RX_72") (pintype "passive"))
    )
    (net (code "24") (name "/73") (class "Default")
      (node (ref "DDR1") (pin "87") (pinfunction "87_87") (pintype "passive"))
      (node (ref "U1") (pin "73") (pinfunction "I2S_BCLK_/GPIO90_/UART8_TX_73") (pintype "passive"))
    )
    (net (code "25") (name "/74") (class "Default")
      (node (ref "DDR1") (pin "89") (pinfunction "89_89") (pintype "passive"))
      (node (ref "U1") (pin "74") (pinfunction "I2C_SDA0_/GPIO85_/UART9_RX/__UART8_CTS_74") (pintype "passive"))
    )
    (net (code "26") (name "/75") (class "Default")
      (node (ref "DDR1") (pin "91") (pinfunction "91_91") (pintype "passive"))
      (node (ref "U1") (pin "75") (pinfunction "I2C_SCL0__/GPIO86_/UART9_TX/__UART8_RTS_75") (pintype "passive"))
    )
    (net (code "27") (name "/76") (class "Default")
      (node (ref "DDR1") (pin "93") (pinfunction "93_93") (pintype "passive"))
      (node (ref "U1") (pin "76") (pinfunction "I2S_MCLK_/GPIO91_76") (pintype "passive"))
    )
    (net (code "28") (name "/77") (class "Default")
      (node (ref "DDR1") (pin "95") (pinfunction "95_95") (pintype "passive"))
      (node (ref "U1") (pin "77") (pinfunction "PWM1_/GPIO92_/ADC_YN_77") (pintype "passive"))
    )
    (net (code "29") (name "/78") (class "Default")
      (node (ref "DDR1") (pin "97") (pinfunction "97_97") (pintype "passive"))
      (node (ref "U1") (pin "78") (pinfunction "PWM0/__CAMCLKOUT__/GPIO06_/ADC_XN_78") (pintype "passive"))
    )
    (net (code "30") (name "/79") (class "Default")
      (node (ref "DDR1") (pin "99") (pinfunction "99_99") (pintype "passive"))
      (node (ref "U1") (pin "79") (pinfunction "SPI0_CS2_/GPIO83_/Sdio_Dat3_79") (pintype "passive"))
    )
    (net (code "31") (name "/82") (class "Default")
      (node (ref "DDR1") (pin "101") (pinfunction "101_101") (pintype "passive"))
      (node (ref "U1") (pin "82") (pinfunction "ADC_VREF_82") (pintype "passive"))
    )
    (net (code "32") (name "/85") (class "Default")
      (node (ref "DDR1") (pin "103") (pinfunction "103_103") (pintype "passive"))
      (node (ref "U1") (pin "85") (pinfunction "ADC_D0_85") (pintype "passive"))
    )
    (net (code "33") (name "/86") (class "Default")
      (node (ref "DDR1") (pin "105") (pinfunction "105_105") (pintype "passive"))
      (node (ref "U1") (pin "86") (pinfunction "ADC_D1_86") (pintype "passive"))
    )
    (net (code "34") (name "/87") (class "Default")
      (node (ref "DDR1") (pin "107") (pinfunction "107_107") (pintype "passive"))
      (node (ref "U1") (pin "87") (pinfunction "ADC_XP_87") (pintype "passive"))
    )
    (net (code "35") (name "/88") (class "Default")
      (node (ref "DDR1") (pin "109") (pinfunction "109_109") (pintype "passive"))
      (node (ref "U1") (pin "88") (pinfunction "ADC_YP_88") (pintype "passive"))
    )
    (net (code "36") (name "/89") (class "Default")
      (node (ref "DDR1") (pin "111") (pinfunction "111_111") (pintype "passive"))
      (node (ref "U1") (pin "89") (pinfunction "SPI0_CS3_/GPIO84_/CAMCLKOUT_/UART10_RX/__UART8_DSR_89") (pintype "passive"))
    )
    (net (code "37") (name "/93") (class "Default")
      (node (ref "DDR1") (pin "113") (pinfunction "113_113") (pintype "passive"))
      (node (ref "U1") (pin "93") (pinfunction "SPI0_CS1_/GPIO82_/Sdio_Dat2_/UART10_TX/__UART8_DTR_93") (pintype "passive"))
    )
    (net (code "38") (name "/103") (class "Default")
      (node (ref "DDR1") (pin "115") (pinfunction "115_115") (pintype "passive"))
      (node (ref "U1") (pin "103") (pinfunction "CAMDATA7_/GPIO57_/LCD_R2_/CAN1_TX_/I2C_SCL2_/UART7_RX_103") (pintype "passive"))
    )
    (net (code "39") (name "/104") (class "Default")
      (node (ref "DDR1") (pin "117") (pinfunction "117_117") (pintype "passive"))
      (node (ref "U1") (pin "104") (pinfunction "CAMDATA6_/GPIO56_/LCD_R1_/CAN1_RX_/I2C_SDA2_/UART7_TX_104") (pintype "passive"))
    )
    (net (code "40") (name "/105") (class "Default")
      (node (ref "DDR1") (pin "119") (pinfunction "119_119") (pintype "passive"))
      (node (ref "U1") (pin "105") (pinfunction "CAMDATA5_/GPIO55_/LCD_R0_/CAN0_TX_/I2C_SCL1_/UART8_RX_105") (pintype "passive"))
    )
    (net (code "41") (name "/106") (class "Default")
      (node (ref "DDR1") (pin "121") (pinfunction "121_121") (pintype "passive"))
      (node (ref "U1") (pin "106") (pinfunction "CAMDATA4_/GPIO54_/LCD_G1_/CAN0_RX_/I2C_SDA1_/UART8_TX_106") (pintype "passive"))
    )
    (net (code "42") (name "/107") (class "Default")
      (node (ref "DDR1") (pin "123") (pinfunction "123_123") (pintype "passive"))
      (node (ref "U1") (pin "107") (pinfunction "CAMDATA3_/GPIO53_/LCD_G0_/CAMCLKOUT_/PWM3_/UART9_RX/__UART8_CTS_107") (pintype "passive"))
    )
    (net (code "43") (name "/108") (class "Default")
      (node (ref "DDR1") (pin "125") (pinfunction "125_125") (pintype "passive"))
      (node (ref "U1") (pin "108") (pinfunction "CAMDATA2_/GPIO52_/LCD_B2_/SPI1_CS3_/PWM2_/UART9_TX/__UART8_RTS_108") (pintype "passive"))
    )
    (net (code "44") (name "/109") (class "Default")
      (node (ref "DDR1") (pin "127") (pinfunction "127_127") (pintype "passive"))
      (node (ref "U1") (pin "109") (pinfunction "CAMDATA1_/GPIO51_/LCD_B1_/SPI1_CS2_/I2C_SCL2_/UART10_RX/__UART8_DSR_109") (pintype "passive"))
    )
    (net (code "45") (name "/110") (class "Default")
      (node (ref "DDR1") (pin "129") (pinfunction "129_129") (pintype "passive"))
      (node (ref "U1") (pin "110") (pinfunction "CAMDATA0_/GPIO50_/LCD_B0_/SPI1_CS1_/I2C_SDA2_/UART10_TX/__UART8_DTR_110") (pintype "passive"))
    )
    (net (code "46") (name "/112") (class "Default")
      (node (ref "DDR1") (pin "131") (pinfunction "131_131") (pintype "passive"))
      (node (ref "U1") (pin "112") (pinfunction "CAMHSYNC_/GPIO49_/NAND_RDY3_/SPI1_CS0_/I2C_SCL1_/UART11_RX/__UART8_DCD_112") (pintype "passive"))
    )
    (net (code "47") (name "/113") (class "Default")
      (node (ref "DDR1") (pin "133") (pinfunction "133_133") (pintype "passive"))
      (node (ref "U1") (pin "113") (pinfunction "CAMVSYNC_/GPIO48_/NAND_CE#3_/SPI1_MOSI_/I2C_SDA1_/UART11_TX/__UART8_RI_113") (pintype "passive"))
    )
    (net (code "48") (name "/114") (class "Default")
      (node (ref "DDR1") (pin "135") (pinfunction "135_135") (pintype "passive"))
      (node (ref "U1") (pin "114") (pinfunction "CAMCLKOUT_/GPIO47_/SRAM_A25_/NAND_RDY2_/SPI1_MISO_/PWM3_/UART6_RX/__UART0_DCD_114") (pintype "passive"))
    )
    (net (code "49") (name "/115") (class "Default")
      (node (ref "DDR1") (pin "137") (pinfunction "137_137") (pintype "passive"))
      (node (ref "U1") (pin "115") (pinfunction "CAMPCLKIN_/GPIO46_/SRAM_A24_/NAND_CE#2_/SPI1_CLK_/PWM2_/UART6_TX/__UART0_RI_115") (pintype "passive"))
    )
    (net (code "50") (name "/116") (class "Default")
      (node (ref "DDR1") (pin "139") (pinfunction "139_139") (pintype "passive"))
      (node (ref "U1") (pin "116") (pinfunction "NAND_7_/GPIO20_/SPI1_CS1/__Sdio_Dat2__/MAC_MDIO_/CAMDATA0_/I2C_SCL2_116") (pintype "passive"))
    )
    (net (code "51") (name "/117") (class "Default")
      (node (ref "DDR1") (pin "141") (pinfunction "141_141") (pintype "passive"))
      (node (ref "U1") (pin "117") (pinfunction "NAND_6_/GPIO19_/SPI1_CS2/__Sdio_Dat3__/MAC_MDC_/CAMDATA1_/I2C_SDA2_117") (pintype "passive"))
    )
    (net (code "52") (name "/118(5)") (class "Default")
      (node (ref "R11") (pin "1") (pinfunction "1_1") (pintype "passive"))
      (node (ref "U1") (pin "118") (pinfunction "NAND_5_/GPIO18_/UART1_TX_/UART3_TX_/CAMDATA2_/PWM2_118") (pintype "passive"))
    )
    (net (code "53") (name "/119(4)") (class "Default")
      (node (ref "R10") (pin "1") (pinfunction "1_1") (pintype "passive"))
      (node (ref "U1") (pin "119") (pinfunction "NAND_4_/GPIO17_/UART1_RX_/UART3_RX_/CAMDATA3_/PWM3_119") (pintype "passive"))
    )
    (net (code "54") (name "/120") (class "Default")
      (node (ref "DDR1") (pin "143") (pinfunction "143_143") (pintype "passive"))
      (node (ref "U1") (pin "120") (pinfunction "NAND_3_/GPIO16_/SPI1_CS0/__Sdio_Dat1__/CAN1_TX_/CAMDATA4_/I2S_LRCK_120") (pintype "passive"))
    )
    (net (code "55") (name "/121") (class "Default")
      (node (ref "DDR1") (pin "145") (pinfunction "145_145") (pintype "passive"))
      (node (ref "U1") (pin "121") (pinfunction "NAND_2_/GPIO15_/SPI1_MOSI/__Sdio_Dat0/CAN1_RX_/CAMDATA5_/I2S_DO_121") (pintype "passive"))
    )
    (net (code "56") (name "/122") (class "Default")
      (node (ref "DDR1") (pin "147") (pinfunction "147_147") (pintype "passive"))
      (node (ref "U1") (pin "122") (pinfunction "NAND_1_/GPIO14_/SPI1_MISO/__Sdio_Cmd__/CAN0_TX_/CAMDATA6_/I2S_BCLK_122") (pintype "passive"))
    )
    (net (code "57") (name "/123") (class "Default")
      (node (ref "DDR1") (pin "149") (pinfunction "149_149") (pintype "passive"))
      (node (ref "U1") (pin "123") (pinfunction "NAND_0_/GPIO13_/SPI1_CLK/__Sdio_clk__/CAN0_RX_/CAMDATA7_/I2S_MCLK_/GPIO_123") (pintype "passive"))
    )
    (net (code "58") (name "/127") (class "Default")
      (node (ref "DDR1") (pin "151") (pinfunction "151_151") (pintype "passive"))
      (node (ref "U1") (pin "127") (pinfunction "NAND_RDY_/GPIO07_127") (pintype "passive"))
    )
    (net (code "59") (name "/128") (class "Default")
      (node (ref "DDR1") (pin "153") (pinfunction "153_153") (pintype "passive"))
      (node (ref "U1") (pin "128") (pinfunction "NAND_CLE_/GPIO08_/GPIO_128") (pintype "passive"))
    )
    (net (code "60") (name "/129") (class "Default")
      (node (ref "DDR1") (pin "155") (pinfunction "155_155") (pintype "passive"))
      (node (ref "U1") (pin "129") (pinfunction "NAND_ALE_/GPIO09_/GPIO_129") (pintype "passive"))
    )
    (net (code "61") (name "/130") (class "Default")
      (node (ref "DDR1") (pin "157") (pinfunction "157_157") (pintype "passive"))
      (node (ref "U1") (pin "130") (pinfunction "NAND_RD#_/GPIO10_/GPIO_130") (pintype "passive"))
    )
    (net (code "62") (name "/132") (class "Default")
      (node (ref "DDR1") (pin "159") (pinfunction "159_159") (pintype "passive"))
      (node (ref "U1") (pin "132") (pinfunction "NAND_CE#_/GPIO11_/GPIO_132") (pintype "passive"))
    )
    (net (code "63") (name "/133") (class "Default")
      (node (ref "DDR1") (pin "203") (pinfunction "203_203") (pintype "passive"))
      (node (ref "U1") (pin "133") (pinfunction "NAND_WR#_/GPIO12_/GPIO_133") (pintype "passive"))
    )
    (net (code "64") (name "/134") (class "Default")
      (node (ref "DDR1") (pin "201") (pinfunction "201_201") (pintype "passive"))
      (node (ref "U1") (pin "134") (pinfunction "MAC_TXEN_/GPIO21_/I2S_MCLK_/NAND_CLE_/I2C_SDA2_/CAN0_RX_/UART8_RX_134") (pintype "passive"))
    )
    (net (code "65") (name "/135") (class "Default")
      (node (ref "DDR1") (pin "199") (pinfunction "199_199") (pintype "passive"))
      (node (ref "U1") (pin "135") (pinfunction "MAC_TXD0_/GPIO23_/I2S_DO_/NAND_ALE_/UART0_RX_/CAN1_RX_/UART4_RX/__UART0_CTS_135") (pintype "passive"))
    )
    (net (code "66") (name "/136") (class "Default")
      (node (ref "DDR1") (pin "197") (pinfunction "197_197") (pintype "passive"))
      (node (ref "U1") (pin "136") (pinfunction "MAC_TXD1_/GPIO24_/I2S_LRCK_/NAND_WR#_/UART0_TX_/CAN1_TX_/UART4_TX/__UART0_RTS_136") (pintype "passive"))
    )
    (net (code "67") (name "/137") (class "Default")
      (node (ref "DDR1") (pin "195") (pinfunction "195_195") (pintype "passive"))
      (node (ref "U1") (pin "137") (pinfunction "MAC_RXER_/GPIO25_/I2S_DI_/NAND_RDY0_/I2C_SDA1_/CAMCLKOUT_/UART5_RX/__UART0_DSR_137") (pintype "passive"))
    )
    (net (code "68") (name "/138") (class "Default")
      (node (ref "DDR1") (pin "193") (pinfunction "193_193") (pintype "passive"))
      (node (ref "U1") (pin "138") (pinfunction "MAC_RXDV_/GPIO26_/SPI1_CS3_/NAND_CE#0_/I2C_SCL1_/CAMPCLKIN_/UART5_TX/__UART0_DTR__/GPIO_138") (pintype "passive"))
    )
    (net (code "69") (name "/139") (class "Default")
      (node (ref "DDR1") (pin "191") (pinfunction "191_191") (pintype "passive"))
      (node (ref "U1") (pin "139") (pinfunction "MAC_RXD0_/GPIO27_/I2C_SDA_/PWM2_/UART2_RX_/CAMVSYNC_/UART6_RX/__UART0_DCD__/GPIO_139") (pintype "passive"))
    )
    (net (code "70") (name "/140") (class "Default")
      (node (ref "DDR1") (pin "189") (pinfunction "189_189") (pintype "passive"))
      (node (ref "U1") (pin "140") (pinfunction "MAC_RXD1_/GPIO28_/I2C_SCL_/PWM3_/UART2_TX_/CAMHSYNC_/UART6_TX/__UART0_RI__/GPIO_140") (pintype "passive"))
    )
    (net (code "71") (name "/141") (class "Default")
      (node (ref "DDR1") (pin "187") (pinfunction "187_187") (pintype "passive"))
      (node (ref "U1") (pin "141") (pinfunction "MAC_MDC_/GPIO29_/CAMDATA7_/NAND_CE#1_/PWM2_/I2C_SCL1_/UART8_TX_/GPIO_141") (pintype "passive"))
    )
    (net (code "72") (name "/143") (class "Default")
      (node (ref "DDR1") (pin "185") (pinfunction "185_185") (pintype "passive"))
      (node (ref "U1") (pin "143") (pinfunction "MAC_MDIO_/GPIO30_/CAMDATA6_/NAND_RDY1_/LCD_B0_/I2C_SDA1_/GPIO_143") (pintype "passive"))
    )
    (net (code "73") (name "/144") (class "Default")
      (node (ref "DDR1") (pin "183") (pinfunction "183_183") (pintype "passive"))
      (node (ref "U1") (pin "144") (pinfunction "MAC_RXD2_/GPIO31_/CAMDATA5_/NAND_CS#2_/LCD_B1_/CAN1_RX_/UART11_RX/__UART8_DCD__/GPIO_144") (pintype "passive"))
    )
    (net (code "74") (name "/145") (class "Default")
      (node (ref "D1") (pin "K") (pinfunction "K_K") (pintype "passive"))
      (node (ref "U1") (pin "145") (pinfunction "MAC_TXD2_/GPIO32_/CAMDATA4_/NAND_RDY2_/LCD_B2_/CAN1_TX_/UART11_TX/__UART8_RI_145") (pintype "passive"))
    )
    (net (code "75") (name "/146") (class "Default")
      (node (ref "DDR1") (pin "181") (pinfunction "181_181") (pintype "passive"))
      (node (ref "U1") (pin "146") (pinfunction "MAC_RXD3_/GPIO33_/CAMDATA3_/UART3_RX_/LCD_G0_/SPI1_CLK/__Sdio_clk_146") (pintype "passive"))
    )
    (net (code "76") (name "/147") (class "Default")
      (node (ref "DDR1") (pin "179") (pinfunction "179_179") (pintype "passive"))
      (node (ref "U1") (pin "147") (pinfunction "MAC_TXD3_/GPIO34_/CAMDATA2_/UART3_TX_/LCD_G1_/SPI1_MISO/__Sdio_Cmd_147") (pintype "passive"))
    )
    (net (code "77") (name "/148") (class "Default")
      (node (ref "DDR1") (pin "177") (pinfunction "177_177") (pintype "passive"))
      (node (ref "U1") (pin "148") (pinfunction "MAC_TXC_/GPIO22_/I2S_BCLK_/NAND_RD#_/I2C_SCL2_/CANO_TX_/SDRAM_CS1_148") (pintype "passive"))
    )
    (net (code "78") (name "/151") (class "Default")
      (node (ref "DDR1") (pin "175") (pinfunction "175_175") (pintype "passive"))
      (node (ref "U1") (pin "151") (pinfunction "MAC_CRS__(ONLY_MII)_/GPIO35_/CAMDATA1_/PWM1_/LCD_R0_/SPI1_MOSI/__Sdio_Dat0_151") (pintype "passive"))
    )
    (net (code "79") (name "/157") (class "Default")
      (node (ref "DDR1") (pin "173") (pinfunction "173_173") (pintype "passive"))
      (node (ref "U1") (pin "157") (pinfunction "OTG_DM_157") (pintype "passive"))
    )
    (net (code "80") (name "/158") (class "Default")
      (node (ref "DDR1") (pin "171") (pinfunction "171_171") (pintype "passive"))
      (node (ref "U1") (pin "158") (pinfunction "OTG_DP_158") (pintype "passive"))
    )
    (net (code "81") (name "/160") (class "Default")
      (node (ref "DDR1") (pin "169") (pinfunction "169_169") (pintype "passive"))
      (node (ref "U1") (pin "160") (pinfunction "OTG_VBUS_160") (pintype "passive"))
    )
    (net (code "82") (name "/161") (class "Default")
      (node (ref "DDR1") (pin "167") (pinfunction "167_167") (pintype "passive"))
      (node (ref "U1") (pin "161") (pinfunction "OTG_ID_161") (pintype "passive"))
    )
    (net (code "83") (name "/168") (class "Default")
      (node (ref "DDR1") (pin "165") (pinfunction "165_165") (pintype "passive"))
      (node (ref "U1") (pin "168") (pinfunction "USB_DM_168") (pintype "passive"))
    )
    (net (code "84") (name "/169") (class "Default")
      (node (ref "DDR1") (pin "163") (pinfunction "163_163") (pintype "passive"))
      (node (ref "U1") (pin "169") (pinfunction "USB_DP_169") (pintype "passive"))
    )
    (net (code "85") (name "/CH_CLK_SPI0_CLK") (class "Default")
      (node (ref "U2") (pin "15") (pinfunction "NO1_15") (pintype "passive"))
      (node (ref "U6") (pin "18") (pinfunction "D3_18") (pintype "bidirectional"))
    )
    (net (code "86") (name "/CH_MISO_SPI0_MISO") (class "Default")
      (node (ref "U2") (pin "7") (pinfunction "NO3_7") (pintype "passive"))
      (node (ref "U6") (pin "22") (pinfunction "D7_22") (pintype "bidirectional"))
    )
    (net (code "87") (name "/CH_MOSI_SPI0_MOSI") (class "Default")
      (node (ref "U2") (pin "3") (pinfunction "NO2_3") (pintype "passive"))
      (node (ref "U6") (pin "20") (pinfunction "D5_20") (pintype "bidirectional"))
    )
    (net (code "88") (name "/CH_SDA") (class "Default")
      (node (ref "R25") (pin "1") (pinfunction "1_1") (pintype "passive"))
      (node (ref "S1") (pin "2") (pinfunction "2_2") (pintype "passive"))
      (node (ref "U2") (pin "10") (pinfunction "INB_10") (pintype "passive"))
      (node (ref "U2") (pin "2") (pinfunction "INA_2") (pintype "passive"))
      (node (ref "U6") (pin "23") (pinfunction "SDA_23") (pintype "bidirectional"))
    )
    (net (code "89") (name "/D+") (class "Default")
      (node (ref "J1") (pin "A6") (pinfunction "D+_A6") (pintype "passive"))
      (node (ref "U6") (pin "10") (pinfunction "UD+_10") (pintype "bidirectional"))
    )
    (net (code "90") (name "/D-") (class "Default")
      (node (ref "J1") (pin "A7") (pinfunction "D-_A7") (pintype "passive"))
      (node (ref "U6") (pin "11") (pinfunction "UD-_11") (pintype "bidirectional"))
    )
    (net (code "91") (name "/EJTAG_RST") (class "Default")
      (node (ref "JP1") (pin "1") (pinfunction "1_1") (pintype "passive"))
      (node (ref "R17") (pin "1") (pinfunction "1_1") (pintype "passive"))
      (node (ref "U1") (pin "100") (pinfunction "EJTAG_RST_/GPIO05_/CAMDATA0_/I2C_SCL2_/PWM1_/UART2_TX_/GPIO_100") (pintype "passive"))
    )
    (net (code "92") (name "/EJTAG_SEL") (class "Default")
      (node (ref "R19") (pin "1") (pinfunction "1_1") (pintype "passive"))
      (node (ref "R20") (pin "1") (pinfunction "1_1") (pintype "passive"))
      (node (ref "U1") (pin "95") (pinfunction "EJTAG_SEL_/GPIO00_/CAMCLKOUT_/I2C_SDA0_/CAN0_RX_/UART3_RX_/SDRAM_CS1_/GPIO_95") (pintype "passive"))
    )
    (net (code "93") (name "/EJTAG_TCK") (class "Default")
      (node (ref "JP1") (pin "5") (pinfunction "5_5") (pintype "passive"))
      (node (ref "R6") (pin "2") (pinfunction "2_2") (pintype "passive"))
      (node (ref "U1") (pin "96") (pinfunction "EJTAG_TCK_/GPIO01_/CAMPCLKIN_/I2C_SCL0_/CAN0_TX_/UART3_TX_/GPIO_96") (pintype "passive"))
    )
    (net (code "94") (name "/EJTAG_TDI") (class "Default")
      (node (ref "JP1") (pin "2") (pinfunction "2_2") (pintype "passive"))
      (node (ref "R7") (pin "1") (pinfunction "1_1") (pintype "passive"))
      (node (ref "R8") (pin "1") (pinfunction "1_1") (pintype "passive"))
      (node (ref "U1") (pin "99") (pinfunction "EJTAG_TDI_/GPIO02_/CAMVSYNC_/I2C_SDA1_/CAN1_RX_/UART1_RX_/GPIO_99") (pintype "passive"))
    )
    (net (code "95") (name "/EJTAG_TDO") (class "Default")
      (node (ref "JP1") (pin "3") (pinfunction "3_3") (pintype "passive"))
      (node (ref "R6") (pin "4") (pinfunction "4_4") (pintype "passive"))
      (node (ref "U1") (pin "98") (pinfunction "EJTAG_TDO_/GPIO03_/CAMHSYNC_/I2C_SCL1_/CAN1_TX_/UART1_TX_/GPIO_98") (pintype "passive"))
    )
    (net (code "96") (name "/EJTAG_TMS") (class "Default")
      (node (ref "JP1") (pin "4") (pinfunction "4_4") (pintype "passive"))
      (node (ref "R6") (pin "3") (pinfunction "3_3") (pintype "passive"))
      (node (ref "U1") (pin "97") (pinfunction "EJTAG_TMS_/GPIO04_/CAMDATA1_/I2C_SDA2_/PWM0_/UART2_RX_/GPIO_97") (pintype "passive"))
    )
    (net (code "97") (name "/FLASH_CS0") (class "Default")
      (node (ref "R15") (pin "2") (pinfunction "2_2") (pintype "passive"))
      (node (ref "U2") (pin "12") (pinfunction "COM4_12") (pintype "passive"))
      (node (ref "U4") (pin "1") (pinfunction "~{CS}_1") (pintype "passive"))
    )
    (net (code "98") (name "/JTAG_SEL") (class "Default")
      (node (ref "JP1") (pin "6") (pinfunction "6_6") (pintype "passive"))
      (node (ref "R16") (pin "1") (pinfunction "1_1") (pintype "passive"))
      (node (ref "R18") (pin "1") (pinfunction "1_1") (pintype "passive"))
      (node (ref "U1") (pin "126") (pinfunction "JTAG_SEL_/SDRAM_CS1_/UART6_TX/__UART0_RI_126") (pintype "passive"))
    )
    (net (code "99") (name "/RTCI") (class "Default")
      (node (ref "C14") (pin "2") (pinfunction "2_2") (pintype "passive"))
      (node (ref "R1") (pin "1") (pinfunction "1_1") (pintype "passive"))
      (node (ref "U1") (pin "175") (pinfunction "RTC_CLK_I_175") (pintype "passive"))
      (node (ref "X2") (pin "1") (pinfunction "1_1") (pintype "passive"))
    )
    (net (code "100") (name "/RTCO") (class "Default")
      (node (ref "C15") (pin "2") (pinfunction "2_2") (pintype "passive"))
      (node (ref "R1") (pin "2") (pinfunction "2_2") (pintype "passive"))
      (node (ref "U1") (pin "174") (pinfunction "RTC_CLK_O_174") (pintype "passive"))
      (node (ref "X2") (pin "2") (pinfunction "2_2") (pintype "passive"))
    )
    (net (code "101") (name "/RTC_VDDA") (class "Default")
      (node (ref "DDR1") (pin "161") (pinfunction "161_161") (pintype "passive"))
      (node (ref "U1") (pin "176") (pinfunction "RTC_VR_VDDA_176") (pintype "passive"))
      (node (ref "VD1") (pin "2") (pinfunction "K_2") (pintype "passive"))
    )
    (net (code "102") (name "/SDRAM_A0") (class "Default")
      (node (ref "U1") (pin "67") (pinfunction "SD_A00/__SRAM_A00_67") (pintype "passive"))
      (node (ref "U3") (pin "H7") (pinfunction "A0_H7") (pintype "passive"))
    )
    (net (code "103") (name "/SDRAM_A1") (class "Default")
      (node (ref "U1") (pin "66") (pinfunction "SD_A01/__SRAM_A01_66") (pintype "passive"))
      (node (ref "U3") (pin "H8") (pinfunction "A1_H8") (pintype "passive"))
    )
    (net (code "104") (name "/SDRAM_A2") (class "Default")
      (node (ref "U1") (pin "65") (pinfunction "SD_A02/__SRAM_A02_65") (pintype "passive"))
      (node (ref "U3") (pin "J8") (pinfunction "A2_J8") (pintype "passive"))
    )
    (net (code "105") (name "/SDRAM_A3") (class "Default")
      (node (ref "U1") (pin "64") (pinfunction "SD_A03/__SRAM_A03_64") (pintype "passive"))
      (node (ref "U3") (pin "J7") (pinfunction "A3_J7") (pintype "passive"))
    )
    (net (code "106") (name "/SDRAM_A4") (class "Default")
      (node (ref "U1") (pin "63") (pinfunction "SD_A04/__SRAM_A04_63") (pintype "passive"))
      (node (ref "U3") (pin "J3") (pinfunction "A4_J3") (pintype "passive"))
    )
    (net (code "107") (name "/SDRAM_A5") (class "Default")
      (node (ref "U1") (pin "62") (pinfunction "SD_A05/__SRAM_A05_62") (pintype "passive"))
      (node (ref "U3") (pin "J2") (pinfunction "A5_J2") (pintype "passive"))
    )
    (net (code "108") (name "/SDRAM_A6") (class "Default")
      (node (ref "U1") (pin "61") (pinfunction "SD_A06/__SRAM_A06_61") (pintype "passive"))
      (node (ref "U3") (pin "H3") (pinfunction "A6_H3") (pintype "passive"))
    )
    (net (code "109") (name "/SDRAM_A7") (class "Default")
      (node (ref "U1") (pin "60") (pinfunction "SD_A07/__SRAM_A07_60") (pintype "passive"))
      (node (ref "U3") (pin "H2") (pinfunction "A7_H2") (pintype "passive"))
    )
    (net (code "110") (name "/SDRAM_A8") (class "Default")
      (node (ref "U1") (pin "59") (pinfunction "SD_A08/__SRAM_A08_59") (pintype "passive"))
      (node (ref "U3") (pin "H1") (pinfunction "A8_H1") (pintype "passive"))
    )
    (net (code "111") (name "/SDRAM_A9") (class "Default")
      (node (ref "U1") (pin "58") (pinfunction "SD_A09/__SRAM_A09_58") (pintype "passive"))
      (node (ref "U3") (pin "G3") (pinfunction "A9_G3") (pintype "passive"))
    )
    (net (code "112") (name "/SDRAM_A10") (class "Default")
      (node (ref "U1") (pin "57") (pinfunction "SD_A10/__SRAM_A10_57") (pintype "passive"))
      (node (ref "U3") (pin "H9") (pinfunction "A10_H9") (pintype "passive"))
    )
    (net (code "113") (name "/SDRAM_A11") (class "Default")
      (node (ref "U1") (pin "56") (pinfunction "SD_A11/__SRAM_A11_56") (pintype "passive"))
      (node (ref "U3") (pin "G2") (pinfunction "A11_G2") (pintype "passive"))
    )
    (net (code "114") (name "/SDRAM_A12") (class "Default")
      (node (ref "U1") (pin "55") (pinfunction "SD_A12/__SRAM_A12_55") (pintype "passive"))
    )
    (net (code "115") (name "/SDRAM_BA0") (class "Default")
      (node (ref "U1") (pin "52") (pinfunction "SD_BA0/__SRAM_A17_52") (pintype "passive"))
      (node (ref "U3") (pin "G7") (pinfunction "BA0_G7") (pintype "passive"))
    )
    (net (code "116") (name "/SDRAM_BA1") (class "Default")
      (node (ref "U1") (pin "50") (pinfunction "SD_BA1/__SRAM_A16_50") (pintype "passive"))
      (node (ref "U3") (pin "G8") (pinfunction "BA1_G8") (pintype "passive"))
    )
    (net (code "117") (name "/SDRAM_CKE") (class "Default")
      (node (ref "U1") (pin "53") (pinfunction "SD_CKE/__SRAM_A13_53") (pintype "passive"))
      (node (ref "U3") (pin "F3") (pinfunction "CKE_F3") (pintype "passive"))
    )
    (net (code "118") (name "/SDRAM_CLK") (class "Default")
      (node (ref "U1") (pin "54") (pinfunction "SD_CLK/__SRAM_OEn_54") (pintype "passive"))
      (node (ref "U3") (pin "F2") (pinfunction "CLK_F2") (pintype "passive"))
    )
    (net (code "119") (name "/SDRAM_D0") (class "Default")
      (node (ref "U1") (pin "44") (pinfunction "SD_D00/__SRAM_D00_44") (pintype "passive"))
      (node (ref "U3") (pin "A8") (pinfunction "DQ0_A8") (pintype "passive"))
    )
    (net (code "120") (name "/SDRAM_D1") (class "Default")
      (node (ref "U1") (pin "43") (pinfunction "SD_D01/__SRAM_D01_43") (pintype "passive"))
      (node (ref "U3") (pin "B9") (pinfunction "DQ1_B9") (pintype "passive"))
    )
    (net (code "121") (name "/SDRAM_D2") (class "Default")
      (node (ref "U1") (pin "42") (pinfunction "SD_D02/__SRAM_D02_42") (pintype "passive"))
      (node (ref "U3") (pin "B8") (pinfunction "DQ2_B8") (pintype "passive"))
    )
    (net (code "122") (name "/SDRAM_D3") (class "Default")
      (node (ref "U1") (pin "41") (pinfunction "SD_D03/__SRAM_D03_41") (pintype "passive"))
      (node (ref "U3") (pin "C9") (pinfunction "DQ3_C9") (pintype "passive"))
    )
    (net (code "123") (name "/SDRAM_D4") (class "Default")
      (node (ref "U1") (pin "40") (pinfunction "SD_D04/__SRAM_D04_40") (pintype "passive"))
      (node (ref "U3") (pin "C8") (pinfunction "DQ4_C8") (pintype "passive"))
    )
    (net (code "124") (name "/SDRAM_D5") (class "Default")
      (node (ref "U1") (pin "39") (pinfunction "SD_D05/__SRAM_D05_39") (pintype "passive"))
      (node (ref "U3") (pin "D9") (pinfunction "DQ5_D9") (pintype "passive"))
    )
    (net (code "125") (name "/SDRAM_D6") (class "Default")
      (node (ref "U1") (pin "38") (pinfunction "SD_D06/__SRAM_D06_38") (pintype "passive"))
      (node (ref "U3") (pin "D8") (pinfunction "DQ6_D8") (pintype "passive"))
    )
    (net (code "126") (name "/SDRAM_D7") (class "Default")
      (node (ref "U1") (pin "37") (pinfunction "SD_D07/__SRAM_D07_37") (pintype "passive"))
      (node (ref "U3") (pin "E9") (pinfunction "DQ7_E9") (pintype "passive"))
    )
    (net (code "127") (name "/SDRAM_D8") (class "Default")
      (node (ref "U1") (pin "34") (pinfunction "SD_D08/__SRAM_D08_/GPIO97_/I2S_MCLK_/NAND_CLE_/I2C_SDA2_/CAN0_RX_34") (pintype "passive"))
      (node (ref "U3") (pin "E1") (pinfunction "DQ8_E1") (pintype "passive"))
    )
    (net (code "128") (name "/SDRAM_D9") (class "Default")
      (node (ref "U1") (pin "33") (pinfunction "SD_D09/__SRAM_D09_/GPIO98_/I2S_BCLK_/NAND_RD#_/I2C_SCL2_/CANO_TX_33") (pintype "passive"))
      (node (ref "U3") (pin "D2") (pinfunction "DQ9_D2") (pintype "passive"))
    )
    (net (code "129") (name "/SDRAM_D10") (class "Default")
      (node (ref "U1") (pin "32") (pinfunction "SD_D10/__SRAM_D10__/GPIO99_/I2S_DI_/NAND_ALE_/UART0_RX_/CAN1_RX_32") (pintype "passive"))
      (node (ref "U3") (pin "D1") (pinfunction "DQ10_D1") (pintype "passive"))
    )
    (net (code "130") (name "/SDRAM_D11") (class "Default")
      (node (ref "U1") (pin "31") (pinfunction "SD_D11/__SRAM_D11__/GPIO100_/I2S_LRCK_/NAND_WR#_/UART0_TX_/CAN1_TX_31") (pintype "passive"))
      (node (ref "U3") (pin "C2") (pinfunction "DQ11_C2") (pintype "passive"))
    )
    (net (code "131") (name "/SDRAM_D12") (class "Default")
      (node (ref "U1") (pin "30") (pinfunction "SD_D12/__SRAM_D13/_GPIO101_/UART1_RX_/NAND_RDY_/I2C_SDA1_/PWM0_30") (pintype "passive"))
      (node (ref "U3") (pin "C1") (pinfunction "DQ12_C1") (pintype "passive"))
    )
    (net (code "132") (name "/SDRAM_D13") (class "Default")
      (node (ref "U1") (pin "29") (pinfunction "SD_D13/__SRAM_D13__/GPIO102_/UART1_TX_/NAND_CE#_/I2C_SCL1_/PWM1_29") (pintype "passive"))
      (node (ref "U3") (pin "B2") (pinfunction "DQ13_B2") (pintype "passive"))
    )
    (net (code "133") (name "/SDRAM_D14") (class "Default")
      (node (ref "U1") (pin "28") (pinfunction "SD_D14/__SRAM_D14__/GPIO103_/I2C_SDA/_PWM2_/UART2_RX_/MDC_28") (pintype "passive"))
      (node (ref "U3") (pin "B1") (pinfunction "DQ14_B1") (pintype "passive"))
    )
    (net (code "134") (name "/SDRAM_D15") (class "Default")
      (node (ref "U1") (pin "27") (pinfunction "SD_D15/__SRAM_D15_/GPIO104_/I2C_SCL_/PWM3_/UART2_TX_/MDIO_27") (pintype "passive"))
      (node (ref "U3") (pin "A2") (pinfunction "DQ15_A2") (pintype "passive"))
    )
    (net (code "135") (name "/SDRAM_DQM0") (class "Default")
      (node (ref "U1") (pin "36") (pinfunction "SD_DQM0/__SRAM_BLEn_36") (pintype "passive"))
      (node (ref "U3") (pin "E8") (pinfunction "LDQM_E8") (pintype "passive"))
    )
    (net (code "136") (name "/SDRAM_DQM1") (class "Default")
      (node (ref "U1") (pin "35") (pinfunction "SD_DQM1/__SRAM_BHEn__/GPIO96_/I2S_DO_/PWM1_/XTALI_/UART6_RX/__UART0_DCD_35") (pintype "passive"))
      (node (ref "U3") (pin "F1") (pinfunction "UDQM_F1") (pintype "passive"))
    )
    (net (code "137") (name "/SPI0_CLK") (class "Default")
      (node (ref "R12") (pin "3") (pinfunction "3_3") (pintype "passive"))
      (node (ref "U1") (pin "94") (pinfunction "SPI_CLK_/GPIO78_/Sdio_clk_/UART5_TX/__UART0_DTR_94") (pintype "passive"))
      (node (ref "U2") (pin "1") (pinfunction "NC1_1") (pintype "passive"))
    )
    (net (code "138") (name "/SPI0_CS0") (class "Default")
      (node (ref "U1") (pin "92") (pinfunction "SPI0_CS0_/GPIO81_/Sdio_Dat1_/SDRAM_CS1_/UART5_RX/__UART0_DSR_92") (pintype "passive"))
      (node (ref "U2") (pin "13") (pinfunction "NC4_13") (pintype "passive"))
    )
    (net (code "139") (name "/SPI0_MISO") (class "Default")
      (node (ref "R12") (pin "1") (pinfunction "1_1") (pintype "passive"))
      (node (ref "U1") (pin "90") (pinfunction "SPI0_MISO_/GPIO80_/Sdio_Cmd_/UART4_RX/__UART0_CTS_90") (pintype "passive"))
      (node (ref "U2") (pin "9") (pinfunction "NC3_9") (pintype "passive"))
    )
    (net (code "140") (name "/SPI0_MOSI") (class "Default")
      (node (ref "R12") (pin "2") (pinfunction "2_2") (pintype "passive"))
      (node (ref "U1") (pin "91") (pinfunction "SPI0_MOSI_/GPIO79_/Sdio_Dat0_/UART4_TX/__UART0_RTS_91") (pintype "passive"))
      (node (ref "U2") (pin "5") (pinfunction "NC2_5") (pintype "passive"))
    )
    (net (code "141") (name "/UART2_RX") (class "Default")
      (node (ref "U1") (pin "149") (pinfunction "MAC_COL_/GPIO36_/CAMDATA0_/UART2_RX_/LCD_R1_/SPI1_CS0/__Sdio_Dat1_149") (pintype "passive"))
      (node (ref "U8") (pin "16") (pinfunction "COM1_16") (pintype "passive"))
    )
    (net (code "142") (name "/UART2_RX_ToCH341") (class "Default")
      (node (ref "U6") (pin "5") (pinfunction "ERR#_5") (pintype "passive"))
      (node (ref "U8") (pin "1") (pinfunction "NC1_1") (pintype "passive"))
    )
    (net (code "143") (name "/UART2_RX_ToDDR") (class "Default")
      (node (ref "DDR1") (pin "21") (pinfunction "21_21") (pintype "passive"))
      (node (ref "U8") (pin "15") (pinfunction "NO1_15") (pintype "passive"))
    )
    (net (code "144") (name "/UART2_TX") (class "Default")
      (node (ref "U1") (pin "150") (pinfunction "MAC_RXC_/GPIO37_/PWM3_/UART2_TX_/LCD_R2_/SPI1_CS1/__Sdio_Dat2_150") (pintype "passive"))
      (node (ref "U8") (pin "12") (pinfunction "COM4_12") (pintype "passive"))
    )
    (net (code "145") (name "/UART2_TX_ToCH341") (class "Default")
      (node (ref "U6") (pin "6") (pinfunction "PEMP_6") (pintype "passive"))
      (node (ref "U8") (pin "13") (pinfunction "NC4_13") (pintype "passive"))
    )
    (net (code "146") (name "/UART2_TX_ToDDR") (class "Default")
      (node (ref "DDR1") (pin "17") (pinfunction "17_17") (pintype "passive"))
      (node (ref "U8") (pin "11") (pinfunction "NO4_11") (pintype "passive"))
    )
    (net (code "147") (name "/USART_INA_INB") (class "Default")
      (node (ref "R30") (pin "1") (pinfunction "1_1") (pintype "passive"))
      (node (ref "S2") (pin "2") (pinfunction "2_2") (pintype "passive"))
      (node (ref "U8") (pin "10") (pinfunction "INB_10") (pintype "passive"))
      (node (ref "U8") (pin "2") (pinfunction "INA_2") (pintype "passive"))
    )
    (net (code "148") (name "/W_CLK") (class "Default")
      (node (ref "U2") (pin "16") (pinfunction "COM1_16") (pintype "passive"))
      (node (ref "U4") (pin "6") (pinfunction "CLK_6") (pintype "passive"))
    )
    (net (code "149") (name "/W_MISO") (class "Default")
      (node (ref "U2") (pin "8") (pinfunction "COM3_8") (pintype "passive"))
      (node (ref "U4") (pin "2") (pinfunction "MISO_2") (pintype "passive"))
    )
    (net (code "150") (name "/W_MOSI") (class "Default")
      (node (ref "U2") (pin "4") (pinfunction "COM2_4") (pintype "passive"))
      (node (ref "U4") (pin "5") (pinfunction "MOSI_5") (pintype "passive"))
    )
    (net (code "151") (name "/XTALI") (class "Default")
      (node (ref "C12") (pin "2") (pinfunction "2_2") (pintype "passive"))
      (node (ref "R2") (pin "1") (pinfunction "1_1") (pintype "passive"))
      (node (ref "U1") (pin "1") (pinfunction "XTALI_1") (pintype "passive"))
      (node (ref "X1") (pin "1") (pinfunction "1_1") (pintype "passive"))
    )
    (net (code "152") (name "/XTALO") (class "Default")
      (node (ref "C13") (pin "2") (pinfunction "2_2") (pintype "passive"))
      (node (ref "R2") (pin "2") (pinfunction "2_2") (pintype "passive"))
      (node (ref "U1") (pin "2") (pinfunction "XTAL0_2") (pintype "passive"))
      (node (ref "X1") (pin "3") (pinfunction "3_3") (pintype "passive"))
    )
    (net (code "153") (name "/~{CH_CS}") (class "Default")
      (node (ref "U2") (pin "11") (pinfunction "NO4_11") (pintype "passive"))
      (node (ref "U6") (pin "15") (pinfunction "D0_15") (pintype "bidirectional"))
    )
    (net (code "154") (name "/~{SDRAM_CAS}") (class "Default")
      (node (ref "R13") (pin "7") (pinfunction "7_7") (pintype "passive"))
      (node (ref "U1") (pin "47") (pinfunction "SD_CASn/__SRAM_A15_47") (pintype "passive"))
      (node (ref "U3") (pin "F7") (pinfunction "~{CAS}_F7") (pintype "passive"))
    )
    (net (code "155") (name "/~{SDRAM_CS}") (class "Default")
      (node (ref "R13") (pin "5") (pinfunction "5_5") (pintype "passive"))
      (node (ref "U1") (pin "49") (pinfunction "SD_CSn/__SRAM_CSn_49") (pintype "passive"))
      (node (ref "U3") (pin "G9") (pinfunction "~{CS}_G9") (pintype "passive"))
    )
    (net (code "156") (name "/~{SDRAM_RAS}") (class "Default")
      (node (ref "R13") (pin "6") (pinfunction "6_6") (pintype "passive"))
      (node (ref "U1") (pin "48") (pinfunction "SD_RASn/__SRAM_A14_48") (pintype "passive"))
      (node (ref "U3") (pin "F8") (pinfunction "~{RAS}_F8") (pintype "passive"))
    )
    (net (code "157") (name "/~{SDRAM_WE}") (class "Default")
      (node (ref "R13") (pin "8") (pinfunction "8_8") (pintype "passive"))
      (node (ref "U1") (pin "46") (pinfunction "SD_WEn/__SRAM_WEn_46") (pintype "passive"))
      (node (ref "U3") (pin "F9") (pinfunction "~{WE}_F9") (pintype "passive"))
    )
    (net (code "158") (name "/~{SPI_HOLD}") (class "Default")
      (node (ref "R15") (pin "3") (pinfunction "3_3") (pintype "passive"))
      (node (ref "U4") (pin "7") (pinfunction "~{HOLD}_7") (pintype "passive"))
    )
    (net (code "159") (name "/~{SPI_WP}") (class "Default")
      (node (ref "R15") (pin "1") (pinfunction "1_1") (pintype "passive"))
      (node (ref "U4") (pin "3") (pinfunction "~{WP}_3") (pintype "passive"))
    )
    (net (code "160") (name "/~{SYS_RESET}") (class "Default")
      (node (ref "C26") (pin "2") (pinfunction "2_2") (pintype "passive"))
      (node (ref "R9") (pin "1") (pinfunction "1_1") (pintype "passive"))
      (node (ref "SW1") (pin "1") (pinfunction "1_1") (pintype "passive"))
      (node (ref "U1") (pin "125") (pinfunction "~{SYS_RST}_125") (pintype "passive"))
    )
    (net (code "161") (name "1V2") (class "Default")
      (node (ref "C16") (pin "2") (pinfunction "2_2") (pintype "passive"))
      (node (ref "C17") (pin "2") (pinfunction "2_2") (pintype "passive"))
      (node (ref "C18") (pin "2") (pinfunction "2_2") (pintype "passive"))
      (node (ref "C19") (pin "2") (pinfunction "2_2") (pintype "passive"))
      (node (ref "C20") (pin "2") (pinfunction "2_2") (pintype "passive"))
      (node (ref "C21") (pin "2") (pinfunction "2_2") (pintype "passive"))
      (node (ref "C22") (pin "2") (pinfunction "2_2") (pintype "passive"))
      (node (ref "C23") (pin "2") (pinfunction "2_2") (pintype "passive"))
      (node (ref "C24") (pin "2") (pinfunction "2_2") (pintype "passive"))
      (node (ref "C25") (pin "2") (pinfunction "2_2") (pintype "passive"))
      (node (ref "C46") (pin "1") (pinfunction "1_1") (pintype "passive"))
      (node (ref "DDR1") (pin "46") (pinfunction "46_46") (pintype "passive"))
      (node (ref "DDR1") (pin "48") (pinfunction "48_48") (pintype "passive"))
      (node (ref "L3") (pin "2") (pinfunction "2_2") (pintype "passive"))
      (node (ref "R27") (pin "2") (pinfunction "2_2") (pintype "passive"))
      (node (ref "TP2") (pin "1") (pinfunction "1_1") (pintype "passive"))
      (node (ref "U1") (pin "101") (pinfunction "CORE_VDD_101") (pintype "passive"))
      (node (ref "U1") (pin "11") (pinfunction "CORE_VDD_11") (pintype "passive"))
      (node (ref "U1") (pin "124") (pinfunction "CORE_VDD_124") (pintype "passive"))
      (node (ref "U1") (pin "152") (pinfunction "CORE_VDD_152") (pintype "passive"))
      (node (ref "U1") (pin "154") (pinfunction "OTG_DVDD_154") (pintype "passive"))
      (node (ref "U1") (pin "164") (pinfunction "USB_DVDD_164") (pintype "passive"))
      (node (ref "U1") (pin "171") (pinfunction "PLL_VDD12_171") (pintype "passive"))
      (node (ref "U1") (pin "26") (pinfunction "CORE_VDD_26") (pintype "passive"))
      (node (ref "U1") (pin "68") (pinfunction "CORE_VDD_68") (pintype "passive"))
    )
    (net (code "162") (name "3V3") (class "Default")
      (node (ref "C1") (pin "2") (pinfunction "2_2") (pintype "passive"))
      (node (ref "C2") (pin "2") (pinfunction "2_2") (pintype "passive"))
      (node (ref "C27") (pin "2") (pinfunction "2_2") (pintype "passive"))
      (node (ref "C28") (pin "2") (pinfunction "2_2") (pintype "passive"))
      (node (ref "C29") (pin "2") (pinfunction "2_2") (pintype "passive"))
      (node (ref "C3") (pin "2") (pinfunction "2_2") (pintype "passive"))
      (node (ref "C30") (pin "2") (pinfunction "2_2") (pintype "passive"))
      (node (ref "C31") (pin "2") (pinfunction "2_2") (pintype "passive"))
      (node (ref "C32") (pin "2") (pinfunction "2_2") (pintype "passive"))
      (node (ref "C33") (pin "2") (pinfunction "2_2") (pintype "passive"))
      (node (ref "C34") (pin "2") (pinfunction "2_2") (pintype "passive"))
      (node (ref "C35") (pin "2") (pinfunction "2_2") (pintype "passive"))
      (node (ref "C36") (pin "1") (pinfunction "1_1") (pintype "passive"))
      (node (ref "C37") (pin "1") (pinfunction "1_1") (pintype "passive"))
      (node (ref "C38") (pin "2") (pinfunction "2_2") (pintype "passive"))
      (node (ref "C39") (pin "2") (pinfunction "2_2") (pintype "passive"))
      (node (ref "C4") (pin "2") (pinfunction "2_2") (pintype "passive"))
      (node (ref "C40") (pin "1") (pinfunction "1_1") (pintype "passive"))
      (node (ref "C42") (pin "2") (pinfunction "2_2") (pintype "passive"))
      (node (ref "C43") (pin "2") (pinfunction "2_2") (pintype "passive"))
      (node (ref "C44") (pin "2") (pinfunction "2_2") (pintype "passive"))
      (node (ref "C45") (pin "2") (pinfunction "2_2") (pintype "passive"))
      (node (ref "C47") (pin "2") (pinfunction "2_2") (pintype "passive"))
      (node (ref "C48") (pin "1") (pinfunction "1_1") (pintype "passive"))
      (node (ref "C49") (pin "1") (pinfunction "1_1") (pintype "passive"))
      (node (ref "C5") (pin "2") (pinfunction "2_2") (pintype "passive"))
      (node (ref "C6") (pin "2") (pinfunction "2_2") (pintype "passive"))
      (node (ref "C7") (pin "2") (pinfunction "2_2") (pintype "passive"))
      (node (ref "C8") (pin "2") (pinfunction "2_2") (pintype "passive"))
      (node (ref "C9") (pin "2") (pinfunction "2_2") (pintype "passive"))
      (node (ref "DDR1") (pin "60") (pinfunction "60_60") (pintype "passive"))
      (node (ref "DDR1") (pin "62") (pinfunction "62_62") (pintype "passive"))
      (node (ref "L1") (pin "1") (pinfunction "1_1") (pintype "passive"))
      (node (ref "L2") (pin "2") (pinfunction "2_2") (pintype "passive"))
      (node (ref "R10") (pin "2") (pinfunction "2_2") (pintype "passive"))
      (node (ref "R12") (pin "6") (pinfunction "6_6") (pintype "passive"))
      (node (ref "R12") (pin "7") (pinfunction "7_7") (pintype "passive"))
      (node (ref "R12") (pin "8") (pinfunction "8_8") (pintype "passive"))
      (node (ref "R13") (pin "1") (pinfunction "1_1") (pintype "passive"))
      (node (ref "R13") (pin "2") (pinfunction "2_2") (pintype "passive"))
      (node (ref "R13") (pin "3") (pinfunction "3_3") (pintype "passive"))
      (node (ref "R13") (pin "4") (pinfunction "4_4") (pintype "passive"))
      (node (ref "R15") (pin "5") (pinfunction "5_5") (pintype "passive"))
      (node (ref "R15") (pin "6") (pinfunction "6_6") (pintype "passive"))
      (node (ref "R15") (pin "7") (pinfunction "7_7") (pintype "passive"))
      (node (ref "R15") (pin "8") (pinfunction "8_8") (pintype "passive"))
      (node (ref "R16") (pin "2") (pinfunction "2_2") (pintype "passive"))
      (node (ref "R19") (pin "2") (pinfunction "2_2") (pintype "passive"))
      (node (ref "R22") (pin "2") (pinfunction "2_2") (pintype "passive"))
      (node (ref "R24") (pin "1") (pinfunction "1_1") (pintype "passive"))
      (node (ref "R25") (pin "2") (pinfunction "2_2") (pintype "passive"))
      (node (ref "R26") (pin "1") (pinfunction "1_1") (pintype "passive"))
      (node (ref "R29") (pin "1") (pinfunction "1_1") (pintype "passive"))
      (node (ref "R30") (pin "2") (pinfunction "2_2") (pintype "passive"))
      (node (ref "R5") (pin "2") (pinfunction "2_2") (pintype "passive"))
      (node (ref "R6") (pin "5") (pinfunction "5_5") (pintype "passive"))
      (node (ref "R6") (pin "6") (pinfunction "6_6") (pintype "passive"))
      (node (ref "R6") (pin "7") (pinfunction "7_7") (pintype "passive"))
      (node (ref "R7") (pin "2") (pinfunction "2_2") (pintype "passive"))
      (node (ref "R9") (pin "2") (pinfunction "2_2") (pintype "passive"))
      (node (ref "TP1") (pin "1") (pinfunction "1_1") (pintype "passive"))
      (node (ref "U1") (pin "102") (pinfunction "IO_VDD_102") (pintype "passive"))
      (node (ref "U1") (pin "131") (pinfunction "IO_VDD_131") (pintype "passive"))
      (node (ref "U1") (pin "155") (pinfunction "OTG_VDD33_155") (pintype "passive"))
      (node (ref "U1") (pin "165") (pinfunction "USB_VDD33_165") (pintype "passive"))
      (node (ref "U1") (pin "173") (pinfunction "PLL_VDD33_173") (pintype "passive"))
      (node (ref "U1") (pin "18") (pinfunction "IO_VDD_18") (pintype "passive"))
      (node (ref "U1") (pin "45") (pinfunction "IO_VDD_45") (pintype "passive"))
      (node (ref "U1") (pin "69") (pinfunction "IO_VDD_69") (pintype "passive"))
      (node (ref "U2") (pin "14") (pinfunction "VCC_14") (pintype "passive"))
      (node (ref "U3") (pin "A7") (pinfunction "VDDQ_A7") (pintype "passive"))
      (node (ref "U3") (pin "A9") (pinfunction "VDD_A9") (pintype "passive"))
      (node (ref "U3") (pin "B3") (pinfunction "VDDQ_B3") (pintype "passive"))
      (node (ref "U3") (pin "C7") (pinfunction "VDDQ_C7") (pintype "passive"))
      (node (ref "U3") (pin "D3") (pinfunction "VDDQ_D3") (pintype "passive"))
      (node (ref "U3") (pin "E7") (pinfunction "VDD_E7") (pintype "passive"))
      (node (ref "U3") (pin "J9") (pinfunction "VDD_J9") (pintype "passive"))
      (node (ref "U4") (pin "8") (pinfunction "VCC_8") (pintype "passive"))
      (node (ref "U6") (pin "28") (pinfunction "VCC_28") (pintype "power_in"))
      (node (ref "U6") (pin "9") (pinfunction "V3_9") (pintype "power_in"))
      (node (ref "U7") (pin "4") (pinfunction "IN_4") (pintype "passive"))
      (node (ref "U8") (pin "14") (pinfunction "VCC_14") (pintype "passive"))
      (node (ref "VD1") (pin "1") (pinfunction "A_1") (pintype "passive"))
    )
    (net (code "163") (name "5V") (class "Default")
      (node (ref "C41") (pin "2") (pinfunction "2_2") (pintype "passive"))
      (node (ref "F1") (pin "2") (pinfunction "2_2") (pintype "passive"))
      (node (ref "TP3") (pin "1") (pinfunction "1_1") (pintype "passive"))
      (node (ref "U5") (pin "4") (pinfunction "IN_4") (pintype "passive"))
    )
    (net (code "164") (name "5V1") (class "Default")
      (node (ref "D3") (pin "2") (pinfunction "K_2") (pintype "passive"))
      (node (ref "DDR1") (pin "10") (pinfunction "10_10") (pintype "passive"))
      (node (ref "DDR1") (pin "3") (pinfunction "3_3") (pintype "passive"))
      (node (ref "DDR1") (pin "4") (pinfunction "4_4") (pintype "passive"))
      (node (ref "DDR1") (pin "5") (pinfunction "5_5") (pintype "passive"))
      (node (ref "DDR1") (pin "6") (pinfunction "6_6") (pintype "passive"))
      (node (ref "DDR1") (pin "7") (pinfunction "7_7") (pintype "passive"))
      (node (ref "DDR1") (pin "8") (pinfunction "8_8") (pintype "passive"))
      (node (ref "DDR1") (pin "9") (pinfunction "9_9") (pintype "passive"))
      (node (ref "F1") (pin "1") (pinfunction "1_1") (pintype "passive"))
      (node (ref "J1") (pin "A4") (pinfunction "VBUS_A4") (pintype "passive"))
    )
    (net (code "165") (name "ADC_VDDA") (class "Default")
      (node (ref "C10") (pin "2") (pinfunction "2_2") (pintype "passive"))
      (node (ref "C11") (pin "2") (pinfunction "2_2") (pintype "passive"))
      (node (ref "L1") (pin "2") (pinfunction "2_2") (pintype "passive"))
      (node (ref "U1") (pin "83") (pinfunction "ADC_VDDA_83") (pintype "passive"))
    )
    (net (code "166") (name "GND") (class "Default")
      (node (ref "C1") (pin "1") (pinfunction "1_1") (pintype "passive"))
      (node (ref "C10") (pin "1") (pinfunction "1_1") (pintype "passive"))
      (node (ref "C11") (pin "1") (pinfunction "1_1") (pintype "passive"))
      (node (ref "C12") (pin "1") (pinfunction "1_1") (pintype "passive"))
      (node (ref "C13") (pin "1") (pinfunction "1_1") (pintype "passive"))
      (node (ref "C14") (pin "1") (pinfunction "1_1") (pintype "passive"))
      (node (ref "C15") (pin "1") (pinfunction "1_1") (pintype "passive"))
      (node (ref "C16") (pin "1") (pinfunction "1_1") (pintype "passive"))
      (node (ref "C17") (pin "1") (pinfunction "1_1") (pintype "passive"))
      (node (ref "C18") (pin "1") (pinfunction "1_1") (pintype "passive"))
      (node (ref "C19") (pin "1") (pinfunction "1_1") (pintype "passive"))
      (node (ref "C2") (pin "1") (pinfunction "1_1") (pintype "passive"))
      (node (ref "C20") (pin "1") (pinfunction "1_1") (pintype "passive"))
      (node (ref "C21") (pin "1") (pinfunction "1_1") (pintype "passive"))
      (node (ref "C22") (pin "1") (pinfunction "1_1") (pintype "passive"))
      (node (ref "C23") (pin "1") (pinfunction "1_1") (pintype "passive"))
      (node (ref "C24") (pin "1") (pinfunction "1_1") (pintype "passive"))
      (node (ref "C25") (pin "1") (pinfunction "1_1") (pintype "passive"))
      (node (ref "C26") (pin "1") (pinfunction "1_1") (pintype "passive"))
      (node (ref "C27") (pin "1") (pinfunction "1_1") (pintype "passive"))
      (node (ref "C28") (pin "1") (pinfunction "1_1") (pintype "passive"))
      (node (ref "C29") (pin "1") (pinfunction "1_1") (pintype "passive"))
      (node (ref "C3") (pin "1") (pinfunction "1_1") (pintype "passive"))
      (node (ref "C30") (pin "1") (pinfunction "1_1") (pintype "passive"))
      (node (ref "C31") (pin "1") (pinfunction "1_1") (pintype "passive"))
      (node (ref "C32") (pin "1") (pinfunction "1_1") (pintype "passive"))
      (node (ref "C33") (pin "1") (pinfunction "1_1") (pintype "passive"))
      (node (ref "C34") (pin "1") (pinfunction "1_1") (pintype "passive"))
      (node (ref "C35") (pin "1") (pinfunction "1_1") (pintype "passive"))
      (node (ref "C36") (pin "2") (pinfunction "2_2") (pintype "passive"))
      (node (ref "C37") (pin "2") (pinfunction "2_2") (pintype "passive"))
      (node (ref "C38") (pin "1") (pinfunction "1_1") (pintype "passive"))
      (node (ref "C39") (pin "1") (pinfunction "1_1") (pintype "passive"))
      (node (ref "C4") (pin "1") (pinfunction "1_1") (pintype "passive"))
      (node (ref "C40") (pin "2") (pinfunction "2_2") (pintype "passive"))
      (node (ref "C41") (pin "1") (pinfunction "1_1") (pintype "passive"))
      (node (ref "C43") (pin "1") (pinfunction "1_1") (pintype "passive"))
      (node (ref "C44") (pin "1") (pinfunction "1_1") (pintype "passive"))
      (node (ref "C45") (pin "1") (pinfunction "1_1") (pintype "passive"))
      (node (ref "C46") (pin "2") (pinfunction "2_2") (pintype "passive"))
      (node (ref "C47") (pin "1") (pinfunction "1_1") (pintype "passive"))
      (node (ref "C48") (pin "2") (pinfunction "2_2") (pintype "passive"))
      (node (ref "C49") (pin "2") (pinfunction "2_2") (pintype "passive"))
      (node (ref "C5") (pin "1") (pinfunction "1_1") (pintype "passive"))
      (node (ref "C6") (pin "1") (pinfunction "1_1") (pintype "passive"))
      (node (ref "C7") (pin "1") (pinfunction "1_1") (pintype "passive"))
      (node (ref "C8") (pin "1") (pinfunction "1_1") (pintype "passive"))
      (node (ref "C9") (pin "1") (pinfunction "1_1") (pintype "passive"))
      (node (ref "D2") (pin "K") (pinfunction "K_K") (pintype "passive"))
      (node (ref "D3") (pin "1") (pinfunction "A_1") (pintype "passive"))
      (node (ref "DDR1") (pin "1") (pinfunction "1_1") (pintype "passive"))
      (node (ref "DDR1") (pin "100") (pinfunction "100_100") (pintype "passive"))
      (node (ref "DDR1") (pin "102") (pinfunction "102_102") (pintype "passive"))
      (node (ref "DDR1") (pin "104") (pinfunction "104_104") (pintype "passive"))
      (node (ref "DDR1") (pin "106") (pinfunction "106_106") (pintype "passive"))
      (node (ref "DDR1") (pin "108") (pinfunction "108_108") (pintype "passive"))
      (node (ref "DDR1") (pin "11") (pinfunction "11_11") (pintype "passive"))
      (node (ref "DDR1") (pin "110") (pinfunction "110_110") (pintype "passive"))
      (node (ref "DDR1") (pin "112") (pinfunction "112_112") (pintype "passive"))
      (node (ref "DDR1") (pin "114") (pinfunction "114_114") (pintype "passive"))
      (node (ref "DDR1") (pin "116") (pinfunction "116_116") (pintype "passive"))
      (node (ref "DDR1") (pin "118") (pinfunction "118_118") (pintype "passive"))
      (node (ref "DDR1") (pin "12") (pinfunction "12_12") (pintype "passive"))
      (node (ref "DDR1") (pin "120") (pinfunction "120_120") (pintype "passive"))
      (node (ref "DDR1") (pin "122") (pinfunction "122_122") (pintype "passive"))
      (node (ref "DDR1") (pin "124") (pinfunction "124_124") (pintype "passive"))
      (node (ref "DDR1") (pin "126") (pinfunction "126_126") (pintype "passive"))
      (node (ref "DDR1") (pin "128") (pinfunction "128_128") (pintype "passive"))
      (node (ref "DDR1") (pin "13") (pinfunction "13_13") (pintype "passive"))
      (node (ref "DDR1") (pin "130") (pinfunction "130_130") (pintype "passive"))
      (node (ref "DDR1") (pin "14") (pinfunction "14_14") (pintype "passive"))
      (node (ref "DDR1") (pin "15") (pinfunction "15_15") (pintype "passive"))
      (node (ref "DDR1") (pin "16") (pinfunction "16_16") (pintype "passive"))
      (node (ref "DDR1") (pin "172") (pinfunction "172_172") (pintype "passive"))
      (node (ref "DDR1") (pin "174") (pinfunction "174_174") (pintype "passive"))
      (node (ref "DDR1") (pin "176") (pinfunction "176_176") (pintype "passive"))
      (node (ref "DDR1") (pin "178") (pinfunction "178_178") (pintype "passive"))
      (node (ref "DDR1") (pin "18") (pinfunction "18_18") (pintype "passive"))
      (node (ref "DDR1") (pin "180") (pinfunction "180_180") (pintype "passive"))
      (node (ref "DDR1") (pin "182") (pinfunction "182_182") (pintype "passive"))
      (node (ref "DDR1") (pin "184") (pinfunction "184_184") (pintype "passive"))
      (node (ref "DDR1") (pin "186") (pinfunction "186_186") (pintype "passive"))
      (node (ref "DDR1") (pin "188") (pinfunction "188_188") (pintype "passive"))
      (node (ref "DDR1") (pin "19") (pinfunction "19_19") (pintype "passive"))
      (node (ref "DDR1") (pin "190") (pinfunction "190_190") (pintype "passive"))
      (node (ref "DDR1") (pin "192") (pinfunction "192_192") (pintype "passive"))
      (node (ref "DDR1") (pin "194") (pinfunction "194_194") (pintype "passive"))
      (node (ref "DDR1") (pin "196") (pinfunction "196_196") (pintype "passive"))
      (node (ref "DDR1") (pin "198") (pinfunction "198_198") (pintype "passive"))
      (node (ref "DDR1") (pin "2") (pinfunction "2_2") (pintype "passive"))
      (node (ref "DDR1") (pin "20") (pinfunction "20_20") (pintype "passive"))
      (node (ref "DDR1") (pin "200") (pinfunction "200_200") (pintype "passive"))
      (node (ref "DDR1") (pin "202") (pinfunction "202_202") (pintype "passive"))
      (node (ref "DDR1") (pin "204") (pinfunction "204_204") (pintype "passive"))
      (node (ref "DDR1") (pin "22") (pinfunction "22_22") (pintype "passive"))
      (node (ref "DDR1") (pin "23") (pinfunction "23_23") (pintype "passive"))
      (node (ref "DDR1") (pin "24") (pinfunction "24_24") (pintype "passive"))
      (node (ref "DDR1") (pin "25") (pinfunction "25_25") (pintype "passive"))
      (node (ref "DDR1") (pin "26") (pinfunction "26_26") (pintype "passive"))
      (node (ref "DDR1") (pin "27") (pinfunction "27_27") (pintype "passive"))
      (node (ref "DDR1") (pin "28") (pinfunction "28_28") (pintype "passive"))
      (node (ref "DDR1") (pin "29") (pinfunction "29_29") (pintype "passive"))
      (node (ref "DDR1") (pin "30") (pinfunction "30_30") (pintype "passive"))
      (node (ref "DDR1") (pin "31") (pinfunction "31_31") (pintype "passive"))
      (node (ref "DDR1") (pin "32") (pinfunction "32_32") (pintype "passive"))
      (node (ref "DDR1") (pin "33") (pinfunction "33_33") (pintype "passive"))
      (node (ref "DDR1") (pin "34") (pinfunction "34_34") (pintype "passive"))
      (node (ref "DDR1") (pin "35") (pinfunction "35_35") (pintype "passive"))
      (node (ref "DDR1") (pin "36") (pinfunction "36_36") (pintype "passive"))
      (node (ref "DDR1") (pin "37") (pinfunction "37_37") (pintype "passive"))
      (node (ref "DDR1") (pin "38") (pinfunction "38_38") (pintype "passive"))
      (node (ref "DDR1") (pin "39") (pinfunction "39_39") (pintype "passive"))
      (node (ref "DDR1") (pin "40") (pinfunction "40_40") (pintype "passive"))
      (node (ref "DDR1") (pin "41") (pinfunction "41_41") (pintype "passive"))
      (node (ref "DDR1") (pin "42") (pinfunction "42_42") (pintype "passive"))
      (node (ref "DDR1") (pin "43") (pinfunction "43_43") (pintype "passive"))
      (node (ref "DDR1") (pin "44") (pinfunction "44_44") (pintype "passive"))
      (node (ref "DDR1") (pin "45") (pinfunction "45_45") (pintype "passive"))
      (node (ref "DDR1") (pin "47") (pinfunction "47_47") (pintype "passive"))
      (node (ref "DDR1") (pin "49") (pinfunction "49_49") (pintype "passive"))
      (node (ref "DDR1") (pin "50") (pinfunction "50_50") (pintype "passive"))
      (node (ref "DDR1") (pin "51") (pinfunction "51_51") (pintype "passive"))
      (node (ref "DDR1") (pin "52") (pinfunction "52_52") (pintype "passive"))
      (node (ref "DDR1") (pin "53") (pinfunction "53_53") (pintype "passive"))
      (node (ref "DDR1") (pin "54") (pinfunction "54_54") (pintype "passive"))
      (node (ref "DDR1") (pin "55") (pinfunction "55_55") (pintype "passive"))
      (node (ref "DDR1") (pin "56") (pinfunction "56_56") (pintype "passive"))
      (node (ref "DDR1") (pin "57") (pinfunction "57_57") (pintype "passive"))
      (node (ref "DDR1") (pin "58") (pinfunction "58_58") (pintype "passive"))
      (node (ref "DDR1") (pin "59") (pinfunction "59_59") (pintype "passive"))
      (node (ref "DDR1") (pin "61") (pinfunction "61_61") (pintype "passive"))
      (node (ref "DDR1") (pin "63") (pinfunction "63_63") (pintype "passive"))
      (node (ref "DDR1") (pin "64") (pinfunction "64_64") (pintype "passive"))
      (node (ref "DDR1") (pin "65") (pinfunction "65_65") (pintype "passive"))
      (node (ref "DDR1") (pin "66") (pinfunction "66_66") (pintype "passive"))
      (node (ref "DDR1") (pin "67") (pinfunction "67_67") (pintype "passive"))
      (node (ref "DDR1") (pin "68") (pinfunction "68_68") (pintype "passive"))
      (node (ref "DDR1") (pin "69") (pinfunction "69_69") (pintype "passive"))
      (node (ref "DDR1") (pin "70") (pinfunction "70_70") (pintype "passive"))
      (node (ref "DDR1") (pin "71") (pinfunction "71_71") (pintype "passive"))
      (node (ref "DDR1") (pin "72") (pinfunction "72_72") (pintype "passive"))
      (node (ref "DDR1") (pin "73") (pinfunction "73_73") (pintype "passive"))
      (node (ref "DDR1") (pin "74") (pinfunction "74_74") (pintype "passive"))
      (node (ref "DDR1") (pin "75") (pinfunction "75_75") (pintype "passive"))
      (node (ref "DDR1") (pin "76") (pinfunction "76_76") (pintype "passive"))
      (node (ref "DDR1") (pin "77") (pinfunction "77_77") (pintype "passive"))
      (node (ref "DDR1") (pin "78") (pinfunction "78_78") (pintype "passive"))
      (node (ref "DDR1") (pin "79") (pinfunction "79_79") (pintype "passive"))
      (node (ref "DDR1") (pin "80") (pinfunction "80_80") (pintype "passive"))
      (node (ref "DDR1") (pin "82") (pinfunction "82_82") (pintype "passive"))
      (node (ref "DDR1") (pin "84") (pinfunction "84_84") (pintype "passive"))
      (node (ref "DDR1") (pin "86") (pinfunction "86_86") (pintype "passive"))
      (node (ref "DDR1") (pin "88") (pinfunction "88_88") (pintype "passive"))
      (node (ref "DDR1") (pin "90") (pinfunction "90_90") (pintype "passive"))
      (node (ref "DDR1") (pin "92") (pinfunction "92_92") (pintype "passive"))
      (node (ref "DDR1") (pin "94") (pinfunction "94_94") (pintype "passive"))
      (node (ref "DDR1") (pin "96") (pinfunction "96_96") (pintype "passive"))
      (node (ref "DDR1") (pin "98") (pinfunction "98_98") (pintype "passive"))
      (node (ref "J1") (pin "A1") (pinfunction "GND_A1") (pintype "passive"))
      (node (ref "J1") (pin "S1") (pinfunction "GND_S1") (pintype "passive"))
      (node (ref "JP1") (pin "7") (pinfunction "7_7") (pintype "passive"))
      (node (ref "R11") (pin "2") (pinfunction "2_2") (pintype "passive"))
      (node (ref "R14") (pin "1") (pinfunction "1_1") (pintype "passive"))
      (node (ref "R17") (pin "2") (pinfunction "2_2") (pintype "passive"))
      (node (ref "R18") (pin "2") (pinfunction "2_2") (pintype "passive"))
      (node (ref "R20") (pin "2") (pinfunction "2_2") (pintype "passive"))
      (node (ref "R21") (pin "2") (pinfunction "2_2") (pintype "passive"))
      (node (ref "R23") (pin "1") (pinfunction "1_1") (pintype "passive"))
      (node (ref "R28") (pin "1") (pinfunction "1_1") (pintype "passive"))
      (node (ref "R3") (pin "1") (pinfunction "1_1") (pintype "passive"))
      (node (ref "R4") (pin "1") (pinfunction "1_1") (pintype "passive"))
      (node (ref "R8") (pin "2") (pinfunction "2_2") (pintype "passive"))
      (node (ref "S1") (pin "1") (pinfunction "1_1") (pintype "passive"))
      (node (ref "S2") (pin "1") (pinfunction "1_1") (pintype "passive"))
      (node (ref "SW1") (pin "2") (pinfunction "2_2") (pintype "passive"))
      (node (ref "TP4") (pin "1") (pinfunction "1_1") (pintype "passive"))
      (node (ref "U1") (pin "111") (pinfunction "CORE_VSS_111") (pintype "passive"))
      (node (ref "U1") (pin "142") (pinfunction "CORE_VSS_142") (pintype "passive"))
      (node (ref "U1") (pin "153") (pinfunction "OTG_DVSS_153") (pintype "passive"))
      (node (ref "U1") (pin "156") (pinfunction "OTG_VSS33_156") (pintype "passive"))
      (node (ref "U1") (pin "162") (pinfunction "CORE_VSS_162") (pintype "passive"))
      (node (ref "U1") (pin "163") (pinfunction "USB_DVSS_163") (pintype "passive"))
      (node (ref "U1") (pin "166") (pinfunction "USB_VSS33_166") (pintype "passive"))
      (node (ref "U1") (pin "170") (pinfunction "PLL_VSS12_170") (pintype "passive"))
      (node (ref "U1") (pin "172") (pinfunction "PLL_VSS33_172") (pintype "passive"))
      (node (ref "U1") (pin "22") (pinfunction "CORE_VSS_22") (pintype "passive"))
      (node (ref "U1") (pin "51") (pinfunction "CORE_VSS_51") (pintype "passive"))
      (node (ref "U1") (pin "80") (pinfunction "CORE_VSS_80") (pintype "passive"))
      (node (ref "U1") (pin "84") (pinfunction "ADC_VSSA_84") (pintype "passive"))
      (node (ref "U2") (pin "0") (pinfunction "GND_0") (pintype "passive"))
      (node (ref "U2") (pin "6") (pinfunction "GND_6") (pintype "passive"))
      (node (ref "U3") (pin "A1") (pinfunction "GND_A1") (pintype "passive"))
      (node (ref "U3") (pin "A3") (pinfunction "GNDQ_A3") (pintype "passive"))
      (node (ref "U3") (pin "B7") (pinfunction "GNDQ_B7") (pintype "passive"))
      (node (ref "U3") (pin "C3") (pinfunction "GNDQ_C3") (pintype "passive"))
      (node (ref "U3") (pin "D7") (pinfunction "GNDQ_D7") (pintype "passive"))
      (node (ref "U3") (pin "E3") (pinfunction "GND_E3") (pintype "passive"))
      (node (ref "U3") (pin "J1") (pinfunction "GND_J1") (pintype "passive"))
      (node (ref "U4") (pin "4") (pinfunction "GND_4") (pintype "passive"))
      (node (ref "U5") (pin "2") (pinfunction "GND_2") (pintype "passive"))
      (node (ref "U6") (pin "0") (pinfunction "GND_0") (pintype "passive"))
      (node (ref "U6") (pin "12") (pinfunction "GND_12") (pintype "power_in"))
      (node (ref "U6") (pin "13") (pinfunction "XI_13") (pintype "passive"))
      (node (ref "U6") (pin "27") (pinfunction "BUSY_27") (pintype "input"))
      (node (ref "U7") (pin "2") (pinfunction "GND_2") (pintype "passive"))
      (node (ref "U8") (pin "0") (pinfunction "GND_0") (pintype "passive"))
      (node (ref "U8") (pin "6") (pinfunction "GND_6") (pintype "passive"))
      (node (ref "X1") (pin "2") (pinfunction "2_2") (pintype "passive"))
      (node (ref "X1") (pin "4") (pinfunction "4_4") (pintype "passive"))
    )
    (net (code "167") (name "Net-(D1-PadA)") (class "Default")
      (node (ref "D1") (pin "A") (pinfunction "A_A") (pintype "passive"))
      (node (ref "R5") (pin "1") (pinfunction "1_1") (pintype "passive"))
    )
    (net (code "168") (name "Net-(D2-PadA)") (class "Default")
      (node (ref "D2") (pin "A") (pinfunction "A_A") (pintype "passive"))
      (node (ref "R26") (pin "2") (pinfunction "2_2") (pintype "passive"))
    )
    (net (code "169") (name "Net-(U1-ADC_REXT)") (class "Default")
      (node (ref "R14") (pin "2") (pinfunction "2_2") (pintype "passive"))
      (node (ref "U1") (pin "81") (pinfunction "ADC_REXT_81") (pintype "passive"))
    )
    (net (code "170") (name "Net-(U1-OTG_REXT)") (class "Default")
      (node (ref "R4") (pin "2") (pinfunction "2_2") (pintype "passive"))
      (node (ref "U1") (pin "159") (pinfunction "OTG_REXT_159") (pintype "passive"))
    )
    (net (code "171") (name "Net-(U1-USB_REXT)") (class "Default")
      (node (ref "R3") (pin "2") (pinfunction "2_2") (pintype "passive"))
      (node (ref "U1") (pin "167") (pinfunction "USB_REXT_167") (pintype "passive"))
    )
    (net (code "172") (name "Net-(U5-EN)") (class "Default")
      (node (ref "R24") (pin "2") (pinfunction "2_2") (pintype "passive"))
      (node (ref "U5") (pin "1") (pinfunction "EN_1") (pintype "passive"))
    )
    (net (code "173") (name "Net-(U5-FB)") (class "Default")
      (node (ref "R22") (pin "1") (pinfunction "1_1") (pintype "passive"))
      (node (ref "R23") (pin "2") (pinfunction "2_2") (pintype "passive"))
      (node (ref "U5") (pin "5") (pinfunction "FB_5") (pintype "passive"))
    )
    (net (code "174") (name "Net-(U5-LX)") (class "Default")
      (node (ref "L2") (pin "1") (pinfunction "1_1") (pintype "passive"))
      (node (ref "U5") (pin "3") (pinfunction "LX_3") (pintype "passive"))
    )
    (net (code "175") (name "Net-(U6-RSTI)") (class "Default")
      (node (ref "C42") (pin "1") (pinfunction "1_1") (pintype "passive"))
      (node (ref "R21") (pin "1") (pinfunction "1_1") (pintype "passive"))
      (node (ref "U6") (pin "2") (pinfunction "RSTI_2") (pintype "passive"))
    )
    (net (code "176") (name "Net-(U7-EN)") (class "Default")
      (node (ref "R29") (pin "2") (pinfunction "2_2") (pintype "passive"))
      (node (ref "U7") (pin "1") (pinfunction "EN_1") (pintype "passive"))
    )
    (net (code "177") (name "Net-(U7-FB)") (class "Default")
      (node (ref "R27") (pin "1") (pinfunction "1_1") (pintype "passive"))
      (node (ref "R28") (pin "2") (pinfunction "2_2") (pintype "passive"))
      (node (ref "U7") (pin "5") (pinfunction "FB_5") (pintype "passive"))
    )
    (net (code "178") (name "Net-(U7-LX)") (class "Default")
      (node (ref "L3") (pin "1") (pinfunction "1_1") (pintype "passive"))
      (node (ref "U7") (pin "3") (pinfunction "LX_3") (pintype "passive"))
    )
    (net (code "179") (name "unconnected-(J1-CC1-PadA5)") (class "Default")
      (node (ref "J1") (pin "A5") (pinfunction "CC1_A5") (pintype "passive"))
    )
    (net (code "180") (name "unconnected-(J1-CC2-PadB5)") (class "Default")
      (node (ref "J1") (pin "B5") (pinfunction "CC2_B5") (pintype "passive"))
    )
    (net (code "181") (name "unconnected-(J1-SBU1-PadA8)") (class "Default")
      (node (ref "J1") (pin "A8") (pinfunction "SBU1_A8") (pintype "passive"))
    )
    (net (code "182") (name "unconnected-(J1-SBU2-PadB8)") (class "Default")
      (node (ref "J1") (pin "B8") (pinfunction "SBU2_B8") (pintype "passive"))
    )
    (net (code "183") (name "unconnected-(R6-Pad1)") (class "Default")
      (node (ref "R6") (pin "1") (pinfunction "1_1") (pintype "passive"))
    )
    (net (code "184") (name "unconnected-(R6-Pad8)") (class "Default")
      (node (ref "R6") (pin "8") (pinfunction "8_8") (pintype "passive"))
    )
    (net (code "185") (name "unconnected-(R12-Pad4)") (class "Default")
      (node (ref "R12") (pin "4") (pinfunction "4_4") (pintype "passive"))
    )
    (net (code "186") (name "unconnected-(R12-Pad5)") (class "Default")
      (node (ref "R12") (pin "5") (pinfunction "5_5") (pintype "passive"))
    )
    (net (code "187") (name "unconnected-(R15-Pad4)") (class "Default")
      (node (ref "R15") (pin "4") (pinfunction "4_4") (pintype "passive"))
    )
    (net (code "188") (name "unconnected-(S1-Pad3)") (class "Default")
      (node (ref "S1") (pin "3") (pinfunction "3_3") (pintype "passive"))
    )
    (net (code "189") (name "unconnected-(S2-Pad3)") (class "Default")
      (node (ref "S2") (pin "3") (pinfunction "3_3") (pintype "passive"))
    )
    (net (code "190") (name "unconnected-(U3-NC-PadE2)") (class "Default")
      (node (ref "U3") (pin "E2") (pinfunction "NC_E2") (pintype "passive"))
    )
    (net (code "191") (name "unconnected-(U3-NC-PadG1)") (class "Default")
      (node (ref "U3") (pin "G1") (pinfunction "NC_G1") (pintype "passive"))
    )
    (net (code "192") (name "unconnected-(U6-ACK#-Pad7)") (class "Default")
      (node (ref "U6") (pin "7") (pinfunction "ACK#_7") (pintype "passive"))
    )
    (net (code "193") (name "unconnected-(U6-ACT#-Pad1)") (class "Default")
      (node (ref "U6") (pin "1") (pinfunction "ACT#_1") (pintype "output"))
    )
    (net (code "194") (name "unconnected-(U6-AFD#-Pad4)") (class "Default")
      (node (ref "U6") (pin "4") (pinfunction "AFD#_4") (pintype "output"))
    )
    (net (code "195") (name "unconnected-(U6-D1-Pad16)") (class "Default")
      (node (ref "U6") (pin "16") (pinfunction "D1_16") (pintype "bidirectional"))
    )
    (net (code "196") (name "unconnected-(U6-D2-Pad17)") (class "Default")
      (node (ref "U6") (pin "17") (pinfunction "D2_17") (pintype "bidirectional"))
    )
    (net (code "197") (name "unconnected-(U6-D4-Pad19)") (class "Default")
      (node (ref "U6") (pin "19") (pinfunction "D4_19") (pintype "bidirectional"))
    )
    (net (code "198") (name "unconnected-(U6-D6-Pad21)") (class "Default")
      (node (ref "U6") (pin "21") (pinfunction "D6_21") (pintype "bidirectional"))
    )
    (net (code "199") (name "unconnected-(U6-INI#-Pad26)") (class "Default")
      (node (ref "U6") (pin "26") (pinfunction "INI#_26") (pintype "output"))
    )
    (net (code "200") (name "unconnected-(U6-SCL-Pad24)") (class "Default")
      (node (ref "U6") (pin "24") (pinfunction "SCL_24") (pintype "output"))
    )
    (net (code "201") (name "unconnected-(U6-SIN#-Pad3)") (class "Default")
      (node (ref "U6") (pin "3") (pinfunction "SIN#_3") (pintype "output"))
    )
    (net (code "202") (name "unconnected-(U6-SLCT-Pad8)") (class "Default")
      (node (ref "U6") (pin "8") (pinfunction "SLCT_8") (pintype "passive"))
    )
    (net (code "203") (name "unconnected-(U6-STB#-Pad25)") (class "Default")
      (node (ref "U6") (pin "25") (pinfunction "STB#_25") (pintype "output"))
    )
    (net (code "204") (name "unconnected-(U6-XO-Pad14)") (class "Default")
      (node (ref "U6") (pin "14") (pinfunction "XO_14") (pintype "output"))
    )
    (net (code "205") (name "unconnected-(U8-COM2-Pad4)") (class "Default")
      (node (ref "U8") (pin "4") (pinfunction "COM2_4") (pintype "passive"))
    )
    (net (code "206") (name "unconnected-(U8-COM3-Pad8)") (class "Default")
      (node (ref "U8") (pin "8") (pinfunction "COM3_8") (pintype "passive"))
    )
    (net (code "207") (name "unconnected-(U8-NC2-Pad5)") (class "Default")
      (node (ref "U8") (pin "5") (pinfunction "NC2_5") (pintype "passive"))
    )
    (net (code "208") (name "unconnected-(U8-NC3-Pad9)") (class "Default")
      (node (ref "U8") (pin "9") (pinfunction "NC3_9") (pintype "passive"))
    )
    (net (code "209") (name "unconnected-(U8-NO2-Pad3)") (class "Default")
      (node (ref "U8") (pin "3") (pinfunction "NO2_3") (pintype "passive"))
    )
    (net (code "210") (name "unconnected-(U8-NO3-Pad7)") (class "Default")
      (node (ref "U8") (pin "7") (pinfunction "NO3_7") (pintype "passive"))
    )
  )
)
